# io-board-a-8.net
KiCad netlist of a schematic drawn in EAGLE
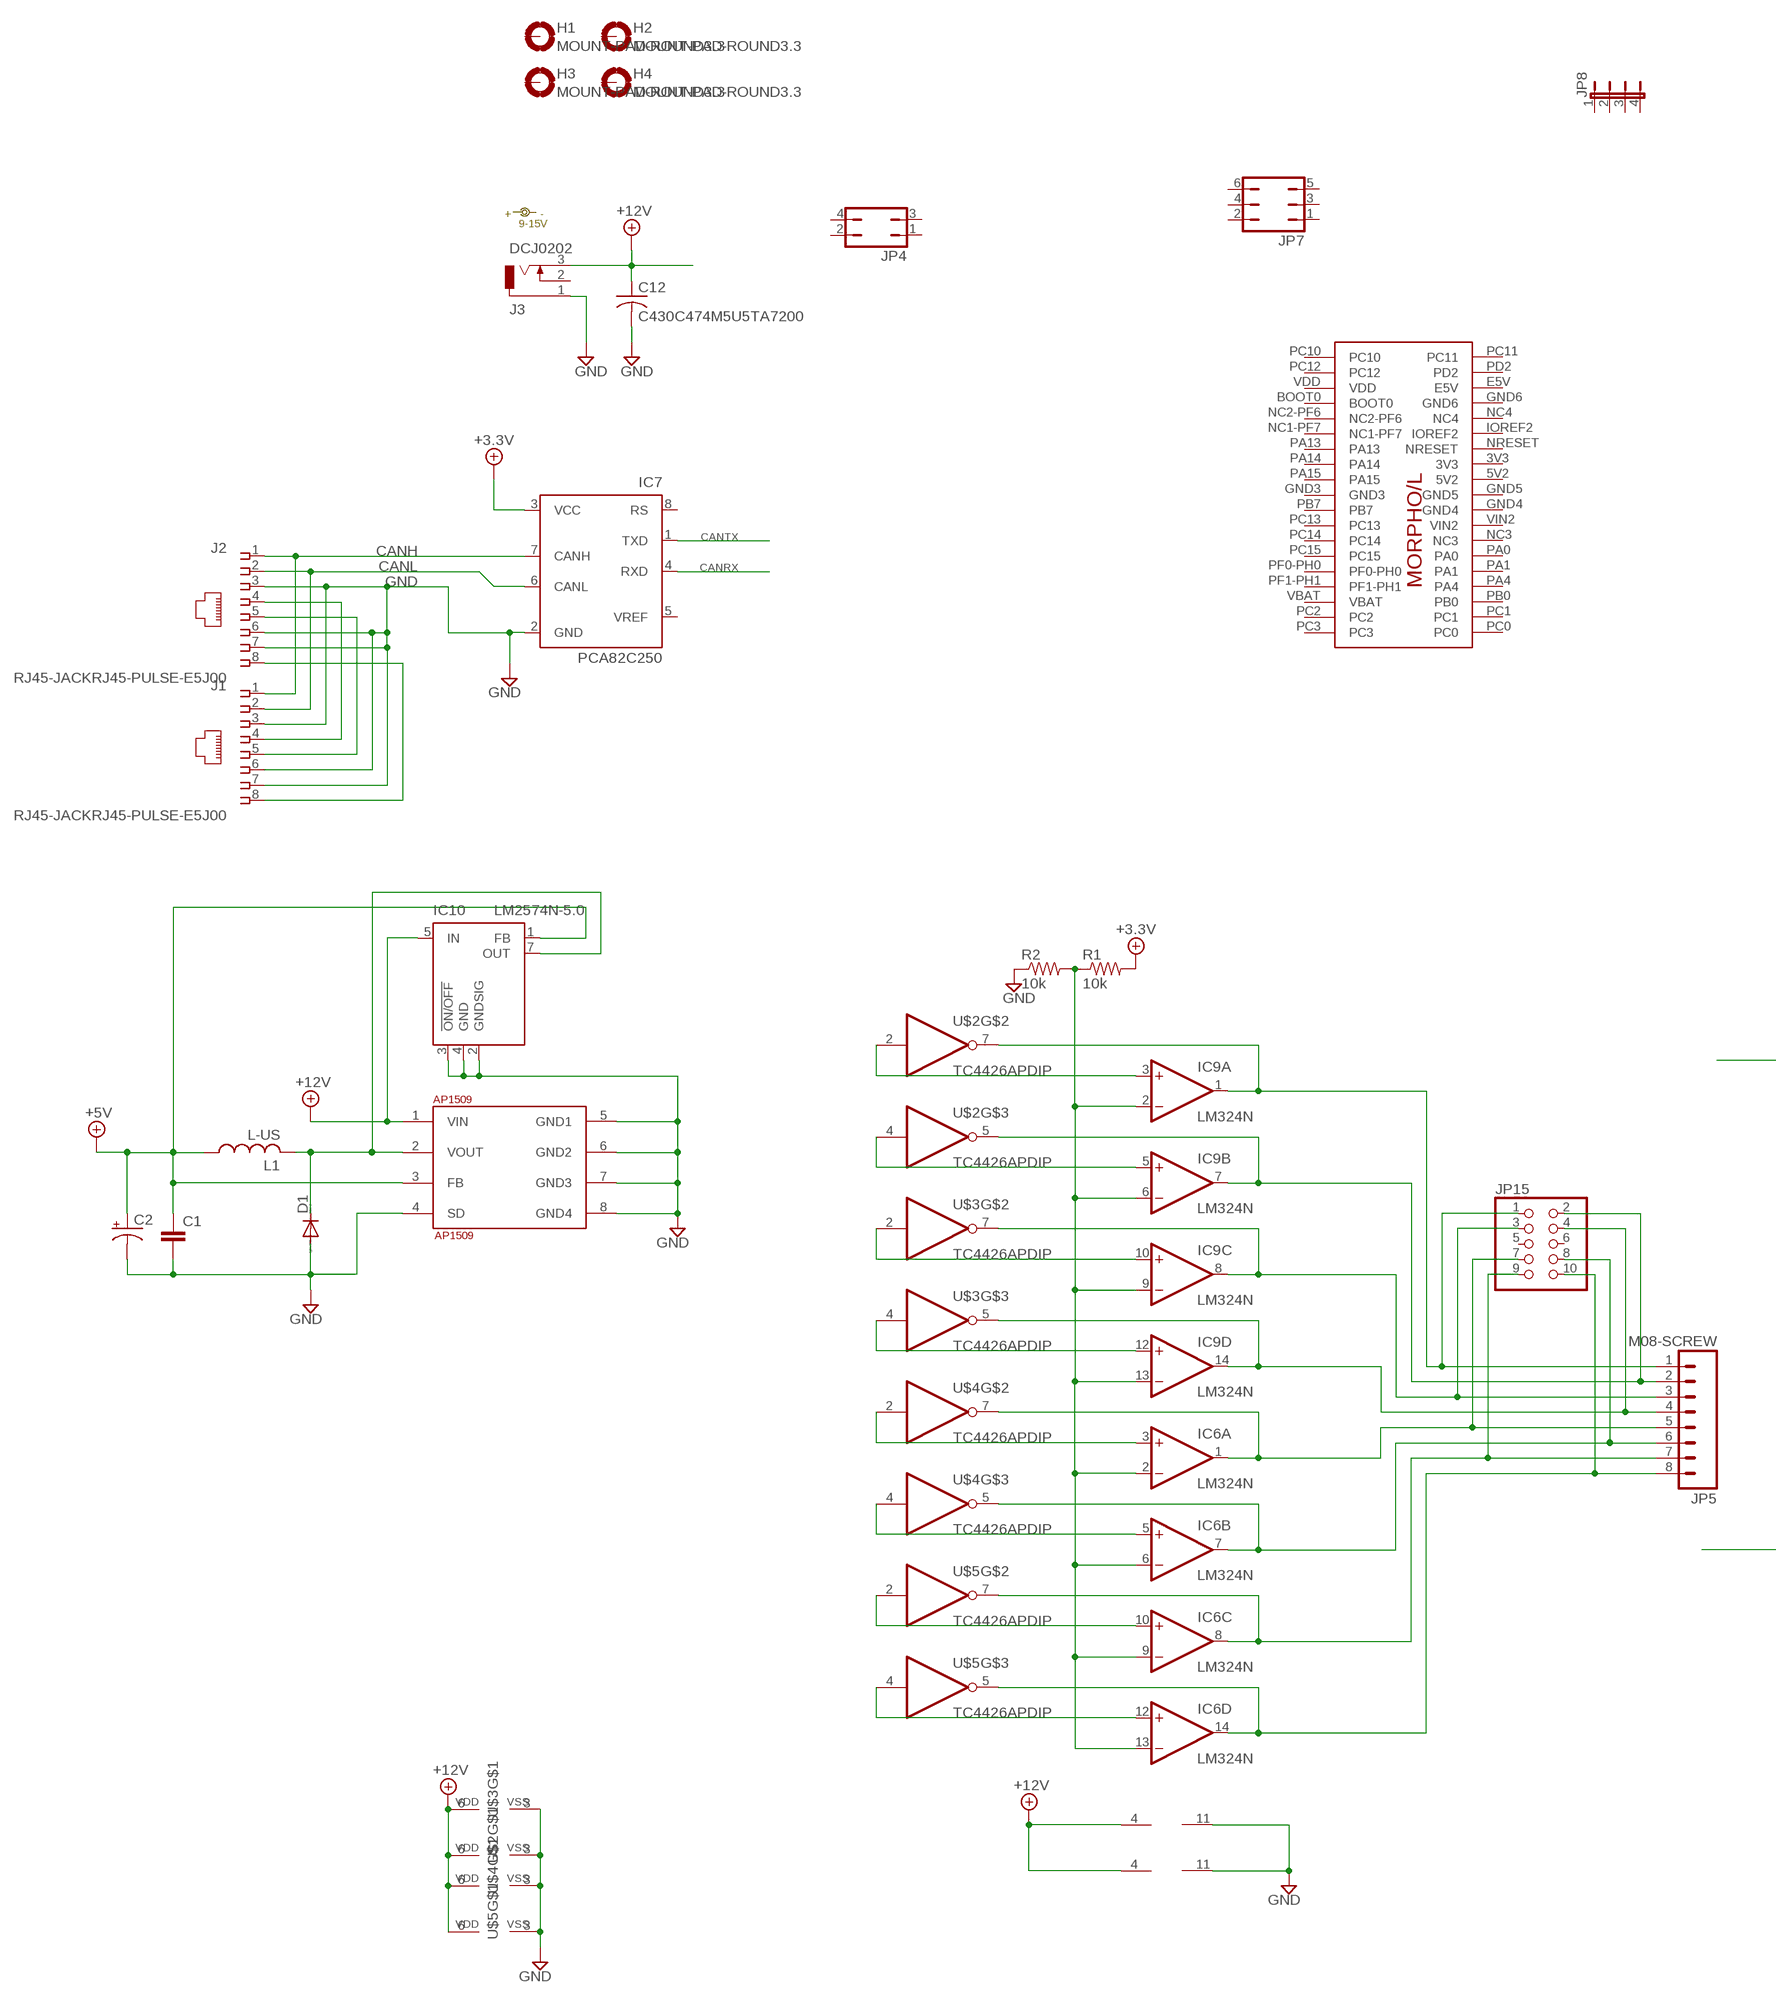
[diagram p0: schematic, sheet 1, part 1 of 2]
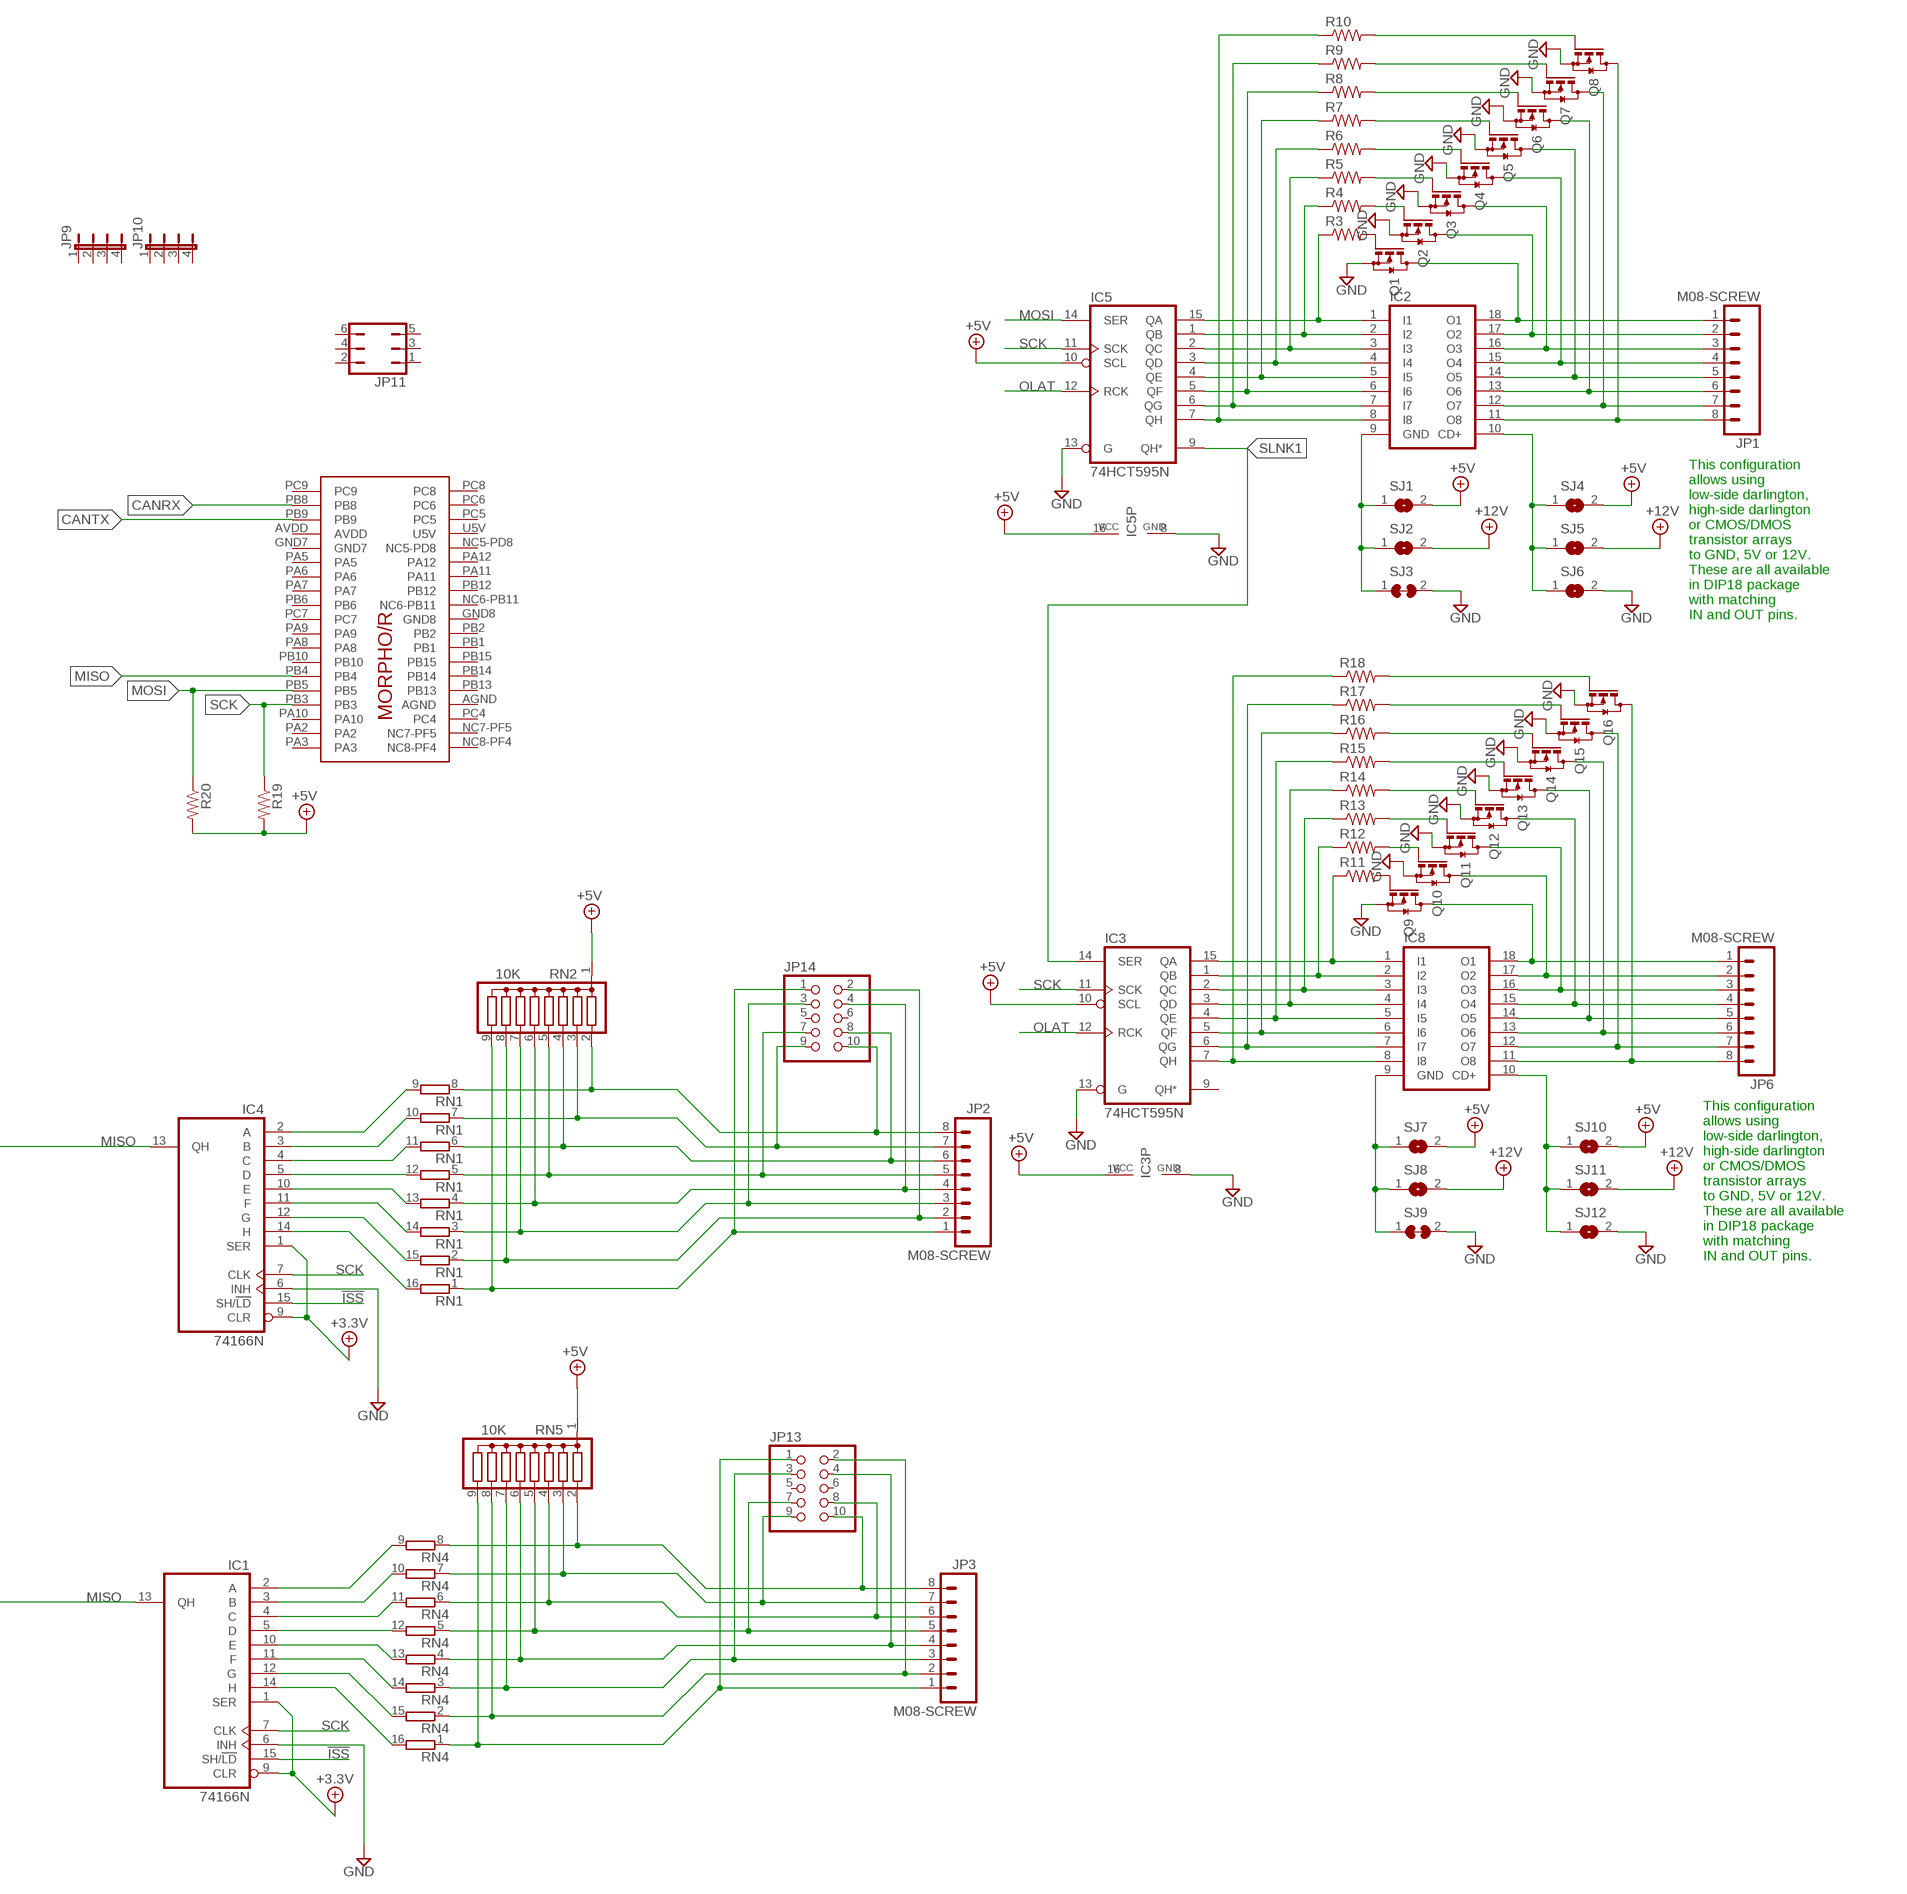
[diagram p1: schematic, sheet 1, part 2 of 2]

(export (version "E")
  (design (tool "Eeschema 10.0.6"))
  (components
    (comp (ref "+12V")
      (value "9-15V")
      (footprint "eagle-import:POWER_USAGE")
      (libsource (lib "eagle-import") (part "DOC-POWER_LABEL"))
    )
    (comp (ref "AP1509")
      (value "AP1509")
      (footprint "eagle-import:SO-08")
      (libsource (lib "eagle-import") (part "AP1509"))
    )
    (comp (ref "C1")
      (value "C-EUC1206")
      (footprint "eagle-import:C1206")
      (libsource (lib "eagle-import") (part "C-EUC1206"))
    )
    (comp (ref "C2")
      (value "CPOL-USE2.5-5")
      (footprint "eagle-import:E2,5-5")
      (libsource (lib "eagle-import") (part "CPOL-USE2.5-5"))
    )
    (comp (ref "C12")
      (value "C430C474M5U5TA7200")
      (footprint "eagle-import:C075-032X103")
      (libsource (lib "eagle-import") (part "C-US075-032X103"))
    )
    (comp (ref "D1")
      (value "DIODE-DO41-7.6")
      (footprint "eagle-import:DO41-7.6")
      (libsource (lib "eagle-import") (part "DIODE-DO41-7.6"))
    )
    (comp (ref "H1")
      (value "MOUNT-PAD-ROUND3.3")
      (footprint "eagle-import:3,3-PAD")
      (libsource (lib "eagle-import") (part "MOUNT-PAD-ROUND3.3"))
    )
    (comp (ref "H2")
      (value "MOUNT-PAD-ROUND3.3")
      (footprint "eagle-import:3,3-PAD")
      (libsource (lib "eagle-import") (part "MOUNT-PAD-ROUND3.3"))
    )
    (comp (ref "H3")
      (value "MOUNT-PAD-ROUND3.3")
      (footprint "eagle-import:3,3-PAD")
      (libsource (lib "eagle-import") (part "MOUNT-PAD-ROUND3.3"))
    )
    (comp (ref "H4")
      (value "MOUNT-PAD-ROUND3.3")
      (footprint "eagle-import:3,3-PAD")
      (libsource (lib "eagle-import") (part "MOUNT-PAD-ROUND3.3"))
    )
    (comp (ref "IC1")
      (value "74166N")
      (footprint "eagle-import:DIL16")
      (libsource (lib "eagle-import") (part "74166N"))
    )
    (comp (ref "IC2")
      (value "ULN2803A")
      (footprint "eagle-import:DIL18-THIN")
      (libsource (lib "eagle-import") (part "ULN2803A"))
    )
    (comp (ref "IC3")
      (value "74HCT595N")
      (footprint "eagle-import:DIL16")
      (libsource (lib "eagle-import") (part "74595NHCT"))
    )
    (comp (ref "IC4")
      (value "74166N")
      (footprint "eagle-import:DIL16")
      (libsource (lib "eagle-import") (part "74166N"))
    )
    (comp (ref "IC5")
      (value "74HCT595N")
      (footprint "eagle-import:DIL16")
      (libsource (lib "eagle-import") (part "74595NHCT"))
    )
    (comp (ref "IC6")
      (value "LM324N")
      (footprint "eagle-import:DIL14")
      (libsource (lib "eagle-import") (part "LM324N"))
    )
    (comp (ref "IC7")
      (value "PCA82C250")
      (footprint "eagle-import:DIL08")
      (libsource (lib "eagle-import") (part "PCA82C250"))
    )
    (comp (ref "IC8")
      (value "ULN2803A")
      (footprint "eagle-import:DIL18-THIN")
      (libsource (lib "eagle-import") (part "ULN2803A"))
    )
    (comp (ref "IC9")
      (value "LM324N")
      (footprint "eagle-import:DIL14")
      (libsource (lib "eagle-import") (part "LM324N"))
    )
    (comp (ref "IC10")
      (value "LM2574N-5.0")
      (footprint "eagle-import:DIL08")
      (libsource (lib "eagle-import") (part "LM2574?-N5.0"))
    )
    (comp (ref "J1")
      (value "RJ45-JACKRJ45-PULSE-E5J00")
      (footprint "eagle-import:RJ45-PULSE-E5J88")
      (libsource (lib "eagle-import") (part "RJ45-JACKRJ45-PULSE-E5J00"))
    )
    (comp (ref "J2")
      (value "RJ45-JACKRJ45-PULSE-E5J00")
      (footprint "eagle-import:RJ45-PULSE-E5J88")
      (libsource (lib "eagle-import") (part "RJ45-JACKRJ45-PULSE-E5J00"))
    )
    (comp (ref "J3")
      (value "DCJ0202")
      (footprint "eagle-import:DCJ0202")
      (libsource (lib "eagle-import") (part "DCJ0202"))
    )
    (comp (ref "JP1")
      (value "M08-SCREW")
      (footprint "eagle-import:1X08_TERMINAL")
      (libsource (lib "eagle-import") (part "M08-SCREW"))
    )
    (comp (ref "JP2")
      (value "M08-SCREW")
      (footprint "eagle-import:1X08_TERMINAL")
      (libsource (lib "eagle-import") (part "M08-SCREW"))
    )
    (comp (ref "JP3")
      (value "M08-SCREW")
      (footprint "eagle-import:1X08_TERMINAL")
      (libsource (lib "eagle-import") (part "M08-SCREW"))
    )
    (comp (ref "JP4")
      (value "JP2Q")
      (footprint "eagle-import:JP2Q")
      (libsource (lib "eagle-import") (part "JP2Q"))
    )
    (comp (ref "JP5")
      (value "M08-SCREW")
      (footprint "eagle-import:1X08_TERMINAL")
      (libsource (lib "eagle-import") (part "M08-SCREW"))
    )
    (comp (ref "JP6")
      (value "M08-SCREW")
      (footprint "eagle-import:1X08_TERMINAL")
      (libsource (lib "eagle-import") (part "M08-SCREW"))
    )
    (comp (ref "JP7")
      (value "JP3Q")
      (footprint "eagle-import:JP3Q")
      (libsource (lib "eagle-import") (part "JP3Q"))
    )
    (comp (ref "JP8")
      (value "JP4-FLAT")
      (footprint "eagle-import:JP4F")
      (libsource (lib "eagle-import") (part "JP4-FLAT"))
    )
    (comp (ref "JP9")
      (value "JP4-FLAT")
      (footprint "eagle-import:JP4F")
      (libsource (lib "eagle-import") (part "JP4-FLAT"))
    )
    (comp (ref "JP10")
      (value "JP4-FLAT")
      (footprint "eagle-import:JP4F")
      (libsource (lib "eagle-import") (part "JP4-FLAT"))
    )
    (comp (ref "JP11")
      (value "JP3Q")
      (footprint "eagle-import:JP3Q")
      (libsource (lib "eagle-import") (part "JP3Q"))
    )
    (comp (ref "JP13")
      (value "PINHD-2X5CN")
      (footprint "eagle-import:CON10M")
      (libsource (lib "eagle-import") (part "PINHD-2X5CN"))
    )
    (comp (ref "JP14")
      (value "PINHD-2X5CN")
      (footprint "eagle-import:CON10M")
      (libsource (lib "eagle-import") (part "PINHD-2X5CN"))
    )
    (comp (ref "JP15")
      (value "PINHD-2X5CN")
      (footprint "eagle-import:CON10M")
      (libsource (lib "eagle-import") (part "PINHD-2X5CN"))
    )
    (comp (ref "L1")
      (value "L-US")
      (footprint "eagle-import:L5-8,5")
      (libsource (lib "eagle-import") (part "L-US"))
    )
    (comp (ref "Q1")
      (value "BSS123")
      (footprint "eagle-import:SOT23")
      (libsource (lib "eagle-import") (part "BSS123"))
    )
    (comp (ref "Q2")
      (value "BSS123")
      (footprint "eagle-import:SOT23")
      (libsource (lib "eagle-import") (part "BSS123"))
    )
    (comp (ref "Q3")
      (value "BSS123")
      (footprint "eagle-import:SOT23")
      (libsource (lib "eagle-import") (part "BSS123"))
    )
    (comp (ref "Q4")
      (value "BSS123")
      (footprint "eagle-import:SOT23")
      (libsource (lib "eagle-import") (part "BSS123"))
    )
    (comp (ref "Q5")
      (value "BSS123")
      (footprint "eagle-import:SOT23")
      (libsource (lib "eagle-import") (part "BSS123"))
    )
    (comp (ref "Q6")
      (value "BSS123")
      (footprint "eagle-import:SOT23")
      (libsource (lib "eagle-import") (part "BSS123"))
    )
    (comp (ref "Q7")
      (value "BSS123")
      (footprint "eagle-import:SOT23")
      (libsource (lib "eagle-import") (part "BSS123"))
    )
    (comp (ref "Q8")
      (value "BSS123")
      (footprint "eagle-import:SOT23")
      (libsource (lib "eagle-import") (part "BSS123"))
    )
    (comp (ref "Q9")
      (value "BSS123")
      (footprint "eagle-import:SOT23")
      (libsource (lib "eagle-import") (part "BSS123"))
    )
    (comp (ref "Q10")
      (value "BSS123")
      (footprint "eagle-import:SOT23")
      (libsource (lib "eagle-import") (part "BSS123"))
    )
    (comp (ref "Q11")
      (value "BSS123")
      (footprint "eagle-import:SOT23")
      (libsource (lib "eagle-import") (part "BSS123"))
    )
    (comp (ref "Q12")
      (value "BSS123")
      (footprint "eagle-import:SOT23")
      (libsource (lib "eagle-import") (part "BSS123"))
    )
    (comp (ref "Q13")
      (value "BSS123")
      (footprint "eagle-import:SOT23")
      (libsource (lib "eagle-import") (part "BSS123"))
    )
    (comp (ref "Q14")
      (value "BSS123")
      (footprint "eagle-import:SOT23")
      (libsource (lib "eagle-import") (part "BSS123"))
    )
    (comp (ref "Q15")
      (value "BSS123")
      (footprint "eagle-import:SOT23")
      (libsource (lib "eagle-import") (part "BSS123"))
    )
    (comp (ref "Q16")
      (value "BSS123")
      (footprint "eagle-import:SOT23")
      (libsource (lib "eagle-import") (part "BSS123"))
    )
    (comp (ref "R1")
      (value "10k")
      (footprint "eagle-import:R1206")
      (libsource (lib "eagle-import") (part "R-US_R1206"))
    )
    (comp (ref "R2")
      (value "10k")
      (footprint "eagle-import:R1206")
      (libsource (lib "eagle-import") (part "R-US_R1206"))
    )
    (comp (ref "R3")
      (value "R-US_R0603")
      (footprint "eagle-import:R0603")
      (libsource (lib "eagle-import") (part "R-US_R0603"))
    )
    (comp (ref "R4")
      (value "R-US_R0603")
      (footprint "eagle-import:R0603")
      (libsource (lib "eagle-import") (part "R-US_R0603"))
    )
    (comp (ref "R5")
      (value "R-US_R0603")
      (footprint "eagle-import:R0603")
      (libsource (lib "eagle-import") (part "R-US_R0603"))
    )
    (comp (ref "R6")
      (value "R-US_R0603")
      (footprint "eagle-import:R0603")
      (libsource (lib "eagle-import") (part "R-US_R0603"))
    )
    (comp (ref "R7")
      (value "R-US_R0603")
      (footprint "eagle-import:R0603")
      (libsource (lib "eagle-import") (part "R-US_R0603"))
    )
    (comp (ref "R8")
      (value "R-US_R0603")
      (footprint "eagle-import:R0603")
      (libsource (lib "eagle-import") (part "R-US_R0603"))
    )
    (comp (ref "R9")
      (value "R-US_R0603")
      (footprint "eagle-import:R0603")
      (libsource (lib "eagle-import") (part "R-US_R0603"))
    )
    (comp (ref "R10")
      (value "R-US_R0603")
      (footprint "eagle-import:R0603")
      (libsource (lib "eagle-import") (part "R-US_R0603"))
    )
    (comp (ref "R11")
      (value "R-US_R0603")
      (footprint "eagle-import:R0603")
      (libsource (lib "eagle-import") (part "R-US_R0603"))
    )
    (comp (ref "R12")
      (value "R-US_R0603")
      (footprint "eagle-import:R0603")
      (libsource (lib "eagle-import") (part "R-US_R0603"))
    )
    (comp (ref "R13")
      (value "R-US_R0603")
      (footprint "eagle-import:R0603")
      (libsource (lib "eagle-import") (part "R-US_R0603"))
    )
    (comp (ref "R14")
      (value "R-US_R0603")
      (footprint "eagle-import:R0603")
      (libsource (lib "eagle-import") (part "R-US_R0603"))
    )
    (comp (ref "R15")
      (value "R-US_R0603")
      (footprint "eagle-import:R0603")
      (libsource (lib "eagle-import") (part "R-US_R0603"))
    )
    (comp (ref "R16")
      (value "R-US_R0603")
      (footprint "eagle-import:R0603")
      (libsource (lib "eagle-import") (part "R-US_R0603"))
    )
    (comp (ref "R17")
      (value "R-US_R0603")
      (footprint "eagle-import:R0603")
      (libsource (lib "eagle-import") (part "R-US_R0603"))
    )
    (comp (ref "R18")
      (value "R-US_R0603")
      (footprint "eagle-import:R0603")
      (libsource (lib "eagle-import") (part "R-US_R0603"))
    )
    (comp (ref "R19")
      (value "R-US_R0805")
      (footprint "eagle-import:R0805")
      (libsource (lib "eagle-import") (part "rcl_334_R-US_R0805"))
    )
    (comp (ref "R20")
      (value "R-US_R0805")
      (footprint "eagle-import:R0805")
      (libsource (lib "eagle-import") (part "rcl_334_R-US_R0805"))
    )
    (comp (ref "RN1")
      (value "8R-P")
      (footprint "eagle-import:DIL16")
      (libsource (lib "eagle-import") (part "8R-P"))
    )
    (comp (ref "RN2")
      (value "10K")
      (footprint "eagle-import:SIL9")
      (libsource (lib "eagle-import") (part "G08R"))
    )
    (comp (ref "RN4")
      (value "8R-P")
      (footprint "eagle-import:DIL16")
      (libsource (lib "eagle-import") (part "8R-P"))
    )
    (comp (ref "RN5")
      (value "10K")
      (footprint "eagle-import:SIL9")
      (libsource (lib "eagle-import") (part "G08R"))
    )
    (comp (ref "SJ1")
      (value "SJ")
      (footprint "eagle-import:SJ-RND")
      (libsource (lib "eagle-import") (part "SJ"))
    )
    (comp (ref "SJ2")
      (value "SJ")
      (footprint "eagle-import:SJ-RND")
      (libsource (lib "eagle-import") (part "SJ"))
    )
    (comp (ref "SJ3")
      (value "SJ-C")
      (footprint "eagle-import:SJW-C")
      (libsource (lib "eagle-import") (part "SJ-C"))
    )
    (comp (ref "SJ4")
      (value "SJ")
      (footprint "eagle-import:SJ-RND")
      (libsource (lib "eagle-import") (part "SJ"))
    )
    (comp (ref "SJ5")
      (value "SJ")
      (footprint "eagle-import:SJ-RND")
      (libsource (lib "eagle-import") (part "SJ"))
    )
    (comp (ref "SJ6")
      (value "SJ")
      (footprint "eagle-import:SJ-RND")
      (libsource (lib "eagle-import") (part "SJ"))
    )
    (comp (ref "SJ7")
      (value "SJ")
      (footprint "eagle-import:SJ-RND")
      (libsource (lib "eagle-import") (part "SJ"))
    )
    (comp (ref "SJ8")
      (value "SJ")
      (footprint "eagle-import:SJ-RND")
      (libsource (lib "eagle-import") (part "SJ"))
    )
    (comp (ref "SJ9")
      (value "SJ-C")
      (footprint "eagle-import:SJW-C")
      (libsource (lib "eagle-import") (part "SJ-C"))
    )
    (comp (ref "SJ10")
      (value "SJ")
      (footprint "eagle-import:SJ-RND")
      (libsource (lib "eagle-import") (part "SJ"))
    )
    (comp (ref "SJ11")
      (value "SJ")
      (footprint "eagle-import:SJ-RND")
      (libsource (lib "eagle-import") (part "SJ"))
    )
    (comp (ref "SJ12")
      (value "SJ")
      (footprint "eagle-import:SJ-RND")
      (libsource (lib "eagle-import") (part "SJ"))
    )
    (comp (ref "U$1")
      (value "NUCLEO_64_GENERIC")
      (footprint "eagle-import:NUCLEO_BRD_BASE64")
      (libsource (lib "eagle-import") (part "NUCLEO_64_GENERIC"))
    )
    (comp (ref "U$2")
      (value "TC4426APDIP")
      (footprint "eagle-import:DIL08-LONG")
      (libsource (lib "eagle-import") (part "TC4426APDIP"))
    )
    (comp (ref "U$3")
      (value "TC4426APDIP")
      (footprint "eagle-import:DIL08-LONG")
      (libsource (lib "eagle-import") (part "TC4426APDIP"))
    )
    (comp (ref "U$4")
      (value "TC4426APDIP")
      (footprint "eagle-import:DIL08-LONG")
      (libsource (lib "eagle-import") (part "TC4426APDIP"))
    )
    (comp (ref "U$5")
      (value "TC4426APDIP")
      (footprint "eagle-import:DIL08-LONG")
      (libsource (lib "eagle-import") (part "TC4426APDIP"))
    )
  )
  (nets
    (net (code "1") (name "+3.3V") (class "Default")
      (node (ref "IC1") (pin "1") (pinfunction "SER_1") (pintype "input"))
      (node (ref "IC1") (pin "9") (pinfunction "CLR_9") (pintype "input"))
      (node (ref "IC4") (pin "1") (pinfunction "SER_1") (pintype "input"))
      (node (ref "IC4") (pin "9") (pinfunction "CLR_9") (pintype "input"))
      (node (ref "IC7") (pin "3") (pinfunction "VCC_3") (pintype "power_in"))
      (node (ref "R1") (pin "2") (pinfunction "2_2") (pintype "passive"))
    )
    (net (code "2") (name "+5V") (class "Default")
      (node (ref "AP1509") (pin "3") (pinfunction "FB_3") (pintype "bidirectional"))
      (node (ref "C1") (pin "1") (pinfunction "1_1") (pintype "passive"))
      (node (ref "C2") (pin "+") (pinfunction "+_+") (pintype "passive"))
      (node (ref "IC10") (pin "1") (pinfunction "FB_1") (pintype "input"))
      (node (ref "IC3") (pin "10") (pinfunction "SCL_10") (pintype "input"))
      (node (ref "IC3") (pin "16") (pinfunction "VCC_16") (pintype "power_in"))
      (node (ref "IC5") (pin "10") (pinfunction "SCL_10") (pintype "input"))
      (node (ref "IC5") (pin "16") (pinfunction "VCC_16") (pintype "power_in"))
      (node (ref "L1") (pin "1") (pinfunction "1_1") (pintype "passive"))
      (node (ref "R19") (pin "2") (pinfunction "2_2") (pintype "passive"))
      (node (ref "R20") (pin "2") (pinfunction "2_2") (pintype "passive"))
      (node (ref "RN2") (pin "1") (pinfunction "1_1") (pintype "passive"))
      (node (ref "RN5") (pin "1") (pinfunction "1_1") (pintype "passive"))
      (node (ref "SJ1") (pin "2") (pinfunction "2_2") (pintype "passive"))
      (node (ref "SJ10") (pin "2") (pinfunction "2_2") (pintype "passive"))
      (node (ref "SJ4") (pin "2") (pinfunction "2_2") (pintype "passive"))
      (node (ref "SJ7") (pin "2") (pinfunction "2_2") (pintype "passive"))
    )
    (net (code "3") (name "+12V") (class "Default")
      (node (ref "AP1509") (pin "1") (pinfunction "VIN_1") (pintype "bidirectional"))
      (node (ref "C12") (pin "1") (pinfunction "1_1") (pintype "passive"))
      (node (ref "IC10") (pin "5") (pinfunction "IN_5") (pintype "input"))
      (node (ref "IC6") (pin "4") (pinfunction "V+_4") (pintype "power_in"))
      (node (ref "IC9") (pin "4") (pinfunction "V+_4") (pintype "power_in"))
      (node (ref "J3") (pin "3") (pinfunction "3_3") (pintype "passive"))
      (node (ref "SJ11") (pin "2") (pinfunction "2_2") (pintype "passive"))
      (node (ref "SJ2") (pin "2") (pinfunction "2_2") (pintype "passive"))
      (node (ref "SJ5") (pin "2") (pinfunction "2_2") (pintype "passive"))
      (node (ref "SJ8") (pin "2") (pinfunction "2_2") (pintype "passive"))
      (node (ref "U$2") (pin "6") (pinfunction "VDD_6") (pintype "power_in"))
      (node (ref "U$3") (pin "6") (pinfunction "VDD_6") (pintype "power_in"))
      (node (ref "U$4") (pin "6") (pinfunction "VDD_6") (pintype "power_in"))
      (node (ref "U$5") (pin "6") (pinfunction "VDD_6") (pintype "power_in"))
    )
    (net (code "4") (name "/3V3") (class "Default")
      (node (ref "U$1") (pin "3V3") (pinfunction "3V3_3V3") (pintype "power_in"))
    )
    (net (code "5") (name "/5V2") (class "Default")
      (node (ref "U$1") (pin "5V2") (pinfunction "5V2_5V2") (pintype "power_in"))
    )
    (net (code "6") (name "/AGND") (class "Default")
      (node (ref "U$1") (pin "AGND") (pinfunction "AGND_AGND") (pintype "power_in"))
    )
    (net (code "7") (name "/AVDD") (class "Default")
      (node (ref "U$1") (pin "AVDD") (pinfunction "AVDD_AVDD") (pintype "power_in"))
    )
    (net (code "8") (name "/CANH") (class "Default")
      (node (ref "IC7") (pin "7") (pinfunction "CANH_7") (pintype "bidirectional"))
      (node (ref "J1") (pin "1") (pinfunction "1_1") (pintype "passive"))
      (node (ref "J2") (pin "1") (pinfunction "1_1") (pintype "passive"))
    )
    (net (code "9") (name "/CANL") (class "Default")
      (node (ref "IC7") (pin "6") (pinfunction "CANL_6") (pintype "bidirectional"))
      (node (ref "J1") (pin "2") (pinfunction "2_2") (pintype "passive"))
      (node (ref "J2") (pin "2") (pinfunction "2_2") (pintype "passive"))
    )
    (net (code "10") (name "/E5V") (class "Default")
      (node (ref "U$1") (pin "E5V") (pinfunction "E5V_E5V") (pintype "power_in"))
    )
    (net (code "11") (name "/GND3") (class "Default")
      (node (ref "U$1") (pin "GND3") (pinfunction "GND3_GND3") (pintype "power_in"))
    )
    (net (code "12") (name "/GND4") (class "Default")
      (node (ref "U$1") (pin "GND4") (pinfunction "GND4_GND4") (pintype "power_in"))
    )
    (net (code "13") (name "/GND5") (class "Default")
      (node (ref "U$1") (pin "GND5") (pinfunction "GND5_GND5") (pintype "power_in"))
    )
    (net (code "14") (name "/GND6") (class "Default")
      (node (ref "U$1") (pin "GND6") (pinfunction "GND6_GND6") (pintype "power_in"))
    )
    (net (code "15") (name "/GND7") (class "Default")
      (node (ref "U$1") (pin "GND7") (pinfunction "GND7_GND7") (pintype "power_in"))
    )
    (net (code "16") (name "/GND8") (class "Default")
      (node (ref "U$1") (pin "GND8") (pinfunction "GND8_GND8") (pintype "power_in"))
    )
    (net (code "17") (name "/OLAT") (class "Default")
      (node (ref "IC3") (pin "12") (pinfunction "RCK_12") (pintype "input"))
      (node (ref "IC5") (pin "12") (pinfunction "RCK_12") (pintype "input"))
    )
    (net (code "18") (name "/U5V") (class "Default")
      (node (ref "U$1") (pin "U5V") (pinfunction "U5V_U5V") (pintype "power_in"))
    )
    (net (code "19") (name "/VBAT") (class "Default")
      (node (ref "U$1") (pin "VBAT") (pinfunction "VBAT_VBAT") (pintype "power_in"))
    )
    (net (code "20") (name "/VDD") (class "Default")
      (node (ref "U$1") (pin "VDD") (pinfunction "VDD_VDD") (pintype "power_in"))
    )
    (net (code "21") (name "/VIN2") (class "Default")
      (node (ref "U$1") (pin "VIN2") (pinfunction "VIN2_VIN2") (pintype "power_in"))
    )
    (net (code "22") (name "/~{ISS}") (class "Default")
      (node (ref "IC1") (pin "15") (pinfunction "SH/~{LD}_15") (pintype "input"))
      (node (ref "IC4") (pin "15") (pinfunction "SH/~{LD}_15") (pintype "input"))
    )
    (net (code "23") (name "CANRX") (class "Default")
      (node (ref "IC7") (pin "4") (pinfunction "RXD_4") (pintype "output"))
      (node (ref "U$1") (pin "PB8") (pinfunction "PB8_PB8") (pintype "bidirectional"))
    )
    (net (code "24") (name "CANTX") (class "Default")
      (node (ref "IC7") (pin "1") (pinfunction "TXD_1") (pintype "input"))
      (node (ref "U$1") (pin "PB9") (pinfunction "PB9_PB9") (pintype "bidirectional"))
    )
    (net (code "25") (name "GND") (class "Default")
      (node (ref "AP1509") (pin "4") (pinfunction "SD_4") (pintype "bidirectional"))
      (node (ref "AP1509") (pin "5") (pinfunction "GND1_5") (pintype "power_in"))
      (node (ref "AP1509") (pin "6") (pinfunction "GND2_6") (pintype "power_in"))
      (node (ref "AP1509") (pin "7") (pinfunction "GND3_7") (pintype "power_in"))
      (node (ref "AP1509") (pin "8") (pinfunction "GND4_8") (pintype "power_in"))
      (node (ref "C1") (pin "2") (pinfunction "2_2") (pintype "passive"))
      (node (ref "C12") (pin "2") (pinfunction "2_2") (pintype "passive"))
      (node (ref "C2") (pin "-") (pinfunction "-_-") (pintype "passive"))
      (node (ref "D1") (pin "A") (pinfunction "A_A") (pintype "passive"))
      (node (ref "IC1") (pin "6") (pinfunction "INH_6") (pintype "input"))
      (node (ref "IC10") (pin "2") (pinfunction "GNDSIG_2") (pintype "input"))
      (node (ref "IC10") (pin "3") (pinfunction "~{ON/OFF}_3") (pintype "input"))
      (node (ref "IC10") (pin "4") (pinfunction "GND_4") (pintype "power_in"))
      (node (ref "IC3") (pin "13") (pinfunction "G_13") (pintype "input"))
      (node (ref "IC3") (pin "8") (pinfunction "GND_8") (pintype "power_in"))
      (node (ref "IC4") (pin "6") (pinfunction "INH_6") (pintype "input"))
      (node (ref "IC5") (pin "13") (pinfunction "G_13") (pintype "input"))
      (node (ref "IC5") (pin "8") (pinfunction "GND_8") (pintype "power_in"))
      (node (ref "IC6") (pin "11") (pinfunction "V-_11") (pintype "power_in"))
      (node (ref "IC7") (pin "2") (pinfunction "GND_2") (pintype "power_in"))
      (node (ref "IC9") (pin "11") (pinfunction "V-_11") (pintype "power_in"))
      (node (ref "J1") (pin "3") (pinfunction "3_3") (pintype "passive"))
      (node (ref "J1") (pin "6") (pinfunction "6_6") (pintype "passive"))
      (node (ref "J1") (pin "7") (pinfunction "7_7") (pintype "passive"))
      (node (ref "J2") (pin "3") (pinfunction "3_3") (pintype "passive"))
      (node (ref "J2") (pin "6") (pinfunction "6_6") (pintype "passive"))
      (node (ref "J2") (pin "7") (pinfunction "7_7") (pintype "passive"))
      (node (ref "J3") (pin "1") (pinfunction "1_1") (pintype "passive"))
      (node (ref "Q1") (pin "2") (pinfunction "S_2") (pintype "passive"))
      (node (ref "Q10") (pin "2") (pinfunction "S_2") (pintype "passive"))
      (node (ref "Q11") (pin "2") (pinfunction "S_2") (pintype "passive"))
      (node (ref "Q12") (pin "2") (pinfunction "S_2") (pintype "passive"))
      (node (ref "Q13") (pin "2") (pinfunction "S_2") (pintype "passive"))
      (node (ref "Q14") (pin "2") (pinfunction "S_2") (pintype "passive"))
      (node (ref "Q15") (pin "2") (pinfunction "S_2") (pintype "passive"))
      (node (ref "Q16") (pin "2") (pinfunction "S_2") (pintype "passive"))
      (node (ref "Q2") (pin "2") (pinfunction "S_2") (pintype "passive"))
      (node (ref "Q3") (pin "2") (pinfunction "S_2") (pintype "passive"))
      (node (ref "Q4") (pin "2") (pinfunction "S_2") (pintype "passive"))
      (node (ref "Q5") (pin "2") (pinfunction "S_2") (pintype "passive"))
      (node (ref "Q6") (pin "2") (pinfunction "S_2") (pintype "passive"))
      (node (ref "Q7") (pin "2") (pinfunction "S_2") (pintype "passive"))
      (node (ref "Q8") (pin "2") (pinfunction "S_2") (pintype "passive"))
      (node (ref "Q9") (pin "2") (pinfunction "S_2") (pintype "passive"))
      (node (ref "R2") (pin "1") (pinfunction "1_1") (pintype "passive"))
      (node (ref "SJ12") (pin "2") (pinfunction "2_2") (pintype "passive"))
      (node (ref "SJ3") (pin "2") (pinfunction "2_2") (pintype "passive"))
      (node (ref "SJ6") (pin "2") (pinfunction "2_2") (pintype "passive"))
      (node (ref "SJ9") (pin "2") (pinfunction "2_2") (pintype "passive"))
      (node (ref "U$2") (pin "3") (pinfunction "VSS_3") (pintype "power_in"))
      (node (ref "U$3") (pin "3") (pinfunction "VSS_3") (pintype "power_in"))
      (node (ref "U$4") (pin "3") (pinfunction "VSS_3") (pintype "power_in"))
      (node (ref "U$5") (pin "3") (pinfunction "VSS_3") (pintype "power_in"))
    )
    (net (code "26") (name "MISO") (class "Default")
      (node (ref "IC1") (pin "13") (pinfunction "QH_13") (pintype "output"))
      (node (ref "IC4") (pin "13") (pinfunction "QH_13") (pintype "output"))
      (node (ref "U$1") (pin "PB4") (pinfunction "PB4_PB4") (pintype "bidirectional"))
    )
    (net (code "27") (name "MOSI") (class "Default")
      (node (ref "IC5") (pin "14") (pinfunction "SER_14") (pintype "input"))
      (node (ref "R20") (pin "1") (pinfunction "1_1") (pintype "passive"))
      (node (ref "U$1") (pin "PB5") (pinfunction "PB5_PB5") (pintype "bidirectional"))
    )
    (net (code "28") (name "Net-(AP1509-VOUT)") (class "Default")
      (node (ref "AP1509") (pin "2") (pinfunction "VOUT_2") (pintype "bidirectional"))
      (node (ref "D1") (pin "C") (pinfunction "C_C") (pintype "passive"))
      (node (ref "IC10") (pin "7") (pinfunction "OUT_7") (pintype "passive"))
      (node (ref "L1") (pin "2") (pinfunction "2_2") (pintype "passive"))
    )
    (net (code "29") (name "Net-(IC1A-A)") (class "Default")
      (node (ref "IC1") (pin "2") (pinfunction "A_2") (pintype "input"))
      (node (ref "RN4") (pin "9") (pinfunction "2_9") (pintype "passive"))
    )
    (net (code "30") (name "Net-(IC1A-B)") (class "Default")
      (node (ref "IC1") (pin "3") (pinfunction "B_3") (pintype "input"))
      (node (ref "RN4") (pin "10") (pinfunction "2_10") (pintype "passive"))
    )
    (net (code "31") (name "Net-(IC1A-C)") (class "Default")
      (node (ref "IC1") (pin "4") (pinfunction "C_4") (pintype "input"))
      (node (ref "RN4") (pin "11") (pinfunction "2_11") (pintype "passive"))
    )
    (net (code "32") (name "Net-(IC1A-D)") (class "Default")
      (node (ref "IC1") (pin "5") (pinfunction "D_5") (pintype "input"))
      (node (ref "RN4") (pin "12") (pinfunction "2_12") (pintype "passive"))
    )
    (net (code "33") (name "Net-(IC1A-E)") (class "Default")
      (node (ref "IC1") (pin "10") (pinfunction "E_10") (pintype "input"))
      (node (ref "RN4") (pin "13") (pinfunction "2_13") (pintype "passive"))
    )
    (net (code "34") (name "Net-(IC1A-F)") (class "Default")
      (node (ref "IC1") (pin "11") (pinfunction "F_11") (pintype "input"))
      (node (ref "RN4") (pin "14") (pinfunction "2_14") (pintype "passive"))
    )
    (net (code "35") (name "Net-(IC1A-G)") (class "Default")
      (node (ref "IC1") (pin "12") (pinfunction "G_12") (pintype "input"))
      (node (ref "RN4") (pin "15") (pinfunction "2_15") (pintype "passive"))
    )
    (net (code "36") (name "Net-(IC1A-H)") (class "Default")
      (node (ref "IC1") (pin "14") (pinfunction "H_14") (pintype "input"))
      (node (ref "RN4") (pin "16") (pinfunction "2_16") (pintype "passive"))
    )
    (net (code "37") (name "Net-(IC2-CD+)") (class "Default")
      (node (ref "IC2") (pin "10") (pinfunction "CD+_10") (pintype "passive"))
      (node (ref "SJ4") (pin "1") (pinfunction "1_1") (pintype "passive"))
      (node (ref "SJ5") (pin "1") (pinfunction "1_1") (pintype "passive"))
      (node (ref "SJ6") (pin "1") (pinfunction "1_1") (pintype "passive"))
    )
    (net (code "38") (name "Net-(IC2-GND)") (class "Default")
      (node (ref "IC2") (pin "9") (pinfunction "GND_9") (pintype "power_in"))
      (node (ref "SJ1") (pin "1") (pinfunction "1_1") (pintype "passive"))
      (node (ref "SJ2") (pin "1") (pinfunction "1_1") (pintype "passive"))
      (node (ref "SJ3") (pin "1") (pinfunction "1_1") (pintype "passive"))
    )
    (net (code "39") (name "Net-(IC2-I1)") (class "Default")
      (node (ref "IC2") (pin "1") (pinfunction "I1_1") (pintype "input"))
      (node (ref "IC5") (pin "15") (pinfunction "QA_15") (pintype "tri_state"))
      (node (ref "R3") (pin "1") (pinfunction "1_1") (pintype "passive"))
    )
    (net (code "40") (name "Net-(IC2-I2)") (class "Default")
      (node (ref "IC2") (pin "2") (pinfunction "I2_2") (pintype "input"))
      (node (ref "IC5") (pin "1") (pinfunction "QB_1") (pintype "tri_state"))
      (node (ref "R4") (pin "1") (pinfunction "1_1") (pintype "passive"))
    )
    (net (code "41") (name "Net-(IC2-I3)") (class "Default")
      (node (ref "IC2") (pin "3") (pinfunction "I3_3") (pintype "input"))
      (node (ref "IC5") (pin "2") (pinfunction "QC_2") (pintype "tri_state"))
      (node (ref "R5") (pin "1") (pinfunction "1_1") (pintype "passive"))
    )
    (net (code "42") (name "Net-(IC2-I4)") (class "Default")
      (node (ref "IC2") (pin "4") (pinfunction "I4_4") (pintype "input"))
      (node (ref "IC5") (pin "3") (pinfunction "QD_3") (pintype "tri_state"))
      (node (ref "R6") (pin "1") (pinfunction "1_1") (pintype "passive"))
    )
    (net (code "43") (name "Net-(IC2-I5)") (class "Default")
      (node (ref "IC2") (pin "5") (pinfunction "I5_5") (pintype "input"))
      (node (ref "IC5") (pin "4") (pinfunction "QE_4") (pintype "tri_state"))
      (node (ref "R7") (pin "1") (pinfunction "1_1") (pintype "passive"))
    )
    (net (code "44") (name "Net-(IC2-I6)") (class "Default")
      (node (ref "IC2") (pin "6") (pinfunction "I6_6") (pintype "input"))
      (node (ref "IC5") (pin "5") (pinfunction "QF_5") (pintype "tri_state"))
      (node (ref "R8") (pin "1") (pinfunction "1_1") (pintype "passive"))
    )
    (net (code "45") (name "Net-(IC2-I7)") (class "Default")
      (node (ref "IC2") (pin "7") (pinfunction "I7_7") (pintype "input"))
      (node (ref "IC5") (pin "6") (pinfunction "QG_6") (pintype "tri_state"))
      (node (ref "R9") (pin "1") (pinfunction "1_1") (pintype "passive"))
    )
    (net (code "46") (name "Net-(IC2-I8)") (class "Default")
      (node (ref "IC2") (pin "8") (pinfunction "I8_8") (pintype "input"))
      (node (ref "IC5") (pin "7") (pinfunction "QH_7") (pintype "tri_state"))
      (node (ref "R10") (pin "1") (pinfunction "1_1") (pintype "passive"))
    )
    (net (code "47") (name "Net-(IC2-O1)") (class "Default")
      (node (ref "IC2") (pin "18") (pinfunction "O1_18") (pintype "open_collector"))
      (node (ref "JP1") (pin "1") (pinfunction "1_1") (pintype "passive"))
      (node (ref "Q1") (pin "3") (pinfunction "D_3") (pintype "passive"))
    )
    (net (code "48") (name "Net-(IC2-O2)") (class "Default")
      (node (ref "IC2") (pin "17") (pinfunction "O2_17") (pintype "open_collector"))
      (node (ref "JP1") (pin "2") (pinfunction "2_2") (pintype "passive"))
      (node (ref "Q2") (pin "3") (pinfunction "D_3") (pintype "passive"))
    )
    (net (code "49") (name "Net-(IC2-O3)") (class "Default")
      (node (ref "IC2") (pin "16") (pinfunction "O3_16") (pintype "open_collector"))
      (node (ref "JP1") (pin "3") (pinfunction "3_3") (pintype "passive"))
      (node (ref "Q3") (pin "3") (pinfunction "D_3") (pintype "passive"))
    )
    (net (code "50") (name "Net-(IC2-O4)") (class "Default")
      (node (ref "IC2") (pin "15") (pinfunction "O4_15") (pintype "open_collector"))
      (node (ref "JP1") (pin "4") (pinfunction "4_4") (pintype "passive"))
      (node (ref "Q4") (pin "3") (pinfunction "D_3") (pintype "passive"))
    )
    (net (code "51") (name "Net-(IC2-O5)") (class "Default")
      (node (ref "IC2") (pin "14") (pinfunction "O5_14") (pintype "open_collector"))
      (node (ref "JP1") (pin "5") (pinfunction "5_5") (pintype "passive"))
      (node (ref "Q5") (pin "3") (pinfunction "D_3") (pintype "passive"))
    )
    (net (code "52") (name "Net-(IC2-O6)") (class "Default")
      (node (ref "IC2") (pin "13") (pinfunction "O6_13") (pintype "open_collector"))
      (node (ref "JP1") (pin "6") (pinfunction "6_6") (pintype "passive"))
      (node (ref "Q6") (pin "3") (pinfunction "D_3") (pintype "passive"))
    )
    (net (code "53") (name "Net-(IC2-O7)") (class "Default")
      (node (ref "IC2") (pin "12") (pinfunction "O7_12") (pintype "open_collector"))
      (node (ref "JP1") (pin "7") (pinfunction "7_7") (pintype "passive"))
      (node (ref "Q7") (pin "3") (pinfunction "D_3") (pintype "passive"))
    )
    (net (code "54") (name "Net-(IC2-O8)") (class "Default")
      (node (ref "IC2") (pin "11") (pinfunction "O8_11") (pintype "open_collector"))
      (node (ref "JP1") (pin "8") (pinfunction "8_8") (pintype "passive"))
      (node (ref "Q8") (pin "3") (pinfunction "D_3") (pintype "passive"))
    )
    (net (code "55") (name "Net-(IC3A-QA)") (class "Default")
      (node (ref "IC3") (pin "15") (pinfunction "QA_15") (pintype "tri_state"))
      (node (ref "IC8") (pin "1") (pinfunction "I1_1") (pintype "input"))
      (node (ref "R11") (pin "1") (pinfunction "1_1") (pintype "passive"))
    )
    (net (code "56") (name "Net-(IC3A-QB)") (class "Default")
      (node (ref "IC3") (pin "1") (pinfunction "QB_1") (pintype "tri_state"))
      (node (ref "IC8") (pin "2") (pinfunction "I2_2") (pintype "input"))
      (node (ref "R12") (pin "1") (pinfunction "1_1") (pintype "passive"))
    )
    (net (code "57") (name "Net-(IC3A-QC)") (class "Default")
      (node (ref "IC3") (pin "2") (pinfunction "QC_2") (pintype "tri_state"))
      (node (ref "IC8") (pin "3") (pinfunction "I3_3") (pintype "input"))
      (node (ref "R13") (pin "1") (pinfunction "1_1") (pintype "passive"))
    )
    (net (code "58") (name "Net-(IC3A-QD)") (class "Default")
      (node (ref "IC3") (pin "3") (pinfunction "QD_3") (pintype "tri_state"))
      (node (ref "IC8") (pin "4") (pinfunction "I4_4") (pintype "input"))
      (node (ref "R14") (pin "1") (pinfunction "1_1") (pintype "passive"))
    )
    (net (code "59") (name "Net-(IC3A-QE)") (class "Default")
      (node (ref "IC3") (pin "4") (pinfunction "QE_4") (pintype "tri_state"))
      (node (ref "IC8") (pin "5") (pinfunction "I5_5") (pintype "input"))
      (node (ref "R15") (pin "1") (pinfunction "1_1") (pintype "passive"))
    )
    (net (code "60") (name "Net-(IC3A-QF)") (class "Default")
      (node (ref "IC3") (pin "5") (pinfunction "QF_5") (pintype "tri_state"))
      (node (ref "IC8") (pin "6") (pinfunction "I6_6") (pintype "input"))
      (node (ref "R16") (pin "1") (pinfunction "1_1") (pintype "passive"))
    )
    (net (code "61") (name "Net-(IC3A-QG)") (class "Default")
      (node (ref "IC3") (pin "6") (pinfunction "QG_6") (pintype "tri_state"))
      (node (ref "IC8") (pin "7") (pinfunction "I7_7") (pintype "input"))
      (node (ref "R17") (pin "1") (pinfunction "1_1") (pintype "passive"))
    )
    (net (code "62") (name "Net-(IC3A-QH)") (class "Default")
      (node (ref "IC3") (pin "7") (pinfunction "QH_7") (pintype "tri_state"))
      (node (ref "IC8") (pin "8") (pinfunction "I8_8") (pintype "input"))
      (node (ref "R18") (pin "1") (pinfunction "1_1") (pintype "passive"))
    )
    (net (code "63") (name "Net-(IC4A-A)") (class "Default")
      (node (ref "IC4") (pin "2") (pinfunction "A_2") (pintype "input"))
      (node (ref "RN1") (pin "9") (pinfunction "2_9") (pintype "passive"))
    )
    (net (code "64") (name "Net-(IC4A-B)") (class "Default")
      (node (ref "IC4") (pin "3") (pinfunction "B_3") (pintype "input"))
      (node (ref "RN1") (pin "10") (pinfunction "2_10") (pintype "passive"))
    )
    (net (code "65") (name "Net-(IC4A-C)") (class "Default")
      (node (ref "IC4") (pin "4") (pinfunction "C_4") (pintype "input"))
      (node (ref "RN1") (pin "11") (pinfunction "2_11") (pintype "passive"))
    )
    (net (code "66") (name "Net-(IC4A-D)") (class "Default")
      (node (ref "IC4") (pin "5") (pinfunction "D_5") (pintype "input"))
      (node (ref "RN1") (pin "12") (pinfunction "2_12") (pintype "passive"))
    )
    (net (code "67") (name "Net-(IC4A-E)") (class "Default")
      (node (ref "IC4") (pin "10") (pinfunction "E_10") (pintype "input"))
      (node (ref "RN1") (pin "13") (pinfunction "2_13") (pintype "passive"))
    )
    (net (code "68") (name "Net-(IC4A-F)") (class "Default")
      (node (ref "IC4") (pin "11") (pinfunction "F_11") (pintype "input"))
      (node (ref "RN1") (pin "14") (pinfunction "2_14") (pintype "passive"))
    )
    (net (code "69") (name "Net-(IC4A-G)") (class "Default")
      (node (ref "IC4") (pin "12") (pinfunction "G_12") (pintype "input"))
      (node (ref "RN1") (pin "15") (pinfunction "2_15") (pintype "passive"))
    )
    (net (code "70") (name "Net-(IC4A-H)") (class "Default")
      (node (ref "IC4") (pin "14") (pinfunction "H_14") (pintype "input"))
      (node (ref "RN1") (pin "16") (pinfunction "2_16") (pintype "passive"))
    )
    (net (code "71") (name "Net-(IC6A-+IN)") (class "Default")
      (node (ref "IC6") (pin "3") (pinfunction "+IN_3") (pintype "input"))
      (node (ref "U$4") (pin "2") (pinfunction "I_2") (pintype "input"))
    )
    (net (code "72") (name "Net-(IC6A--IN)") (class "Default")
      (node (ref "IC6") (pin "13") (pinfunction "-IN_13") (pintype "input"))
      (node (ref "IC6") (pin "2") (pinfunction "-IN_2") (pintype "input"))
      (node (ref "IC6") (pin "6") (pinfunction "-IN_6") (pintype "input"))
      (node (ref "IC6") (pin "9") (pinfunction "-IN_9") (pintype "input"))
      (node (ref "IC9") (pin "13") (pinfunction "-IN_13") (pintype "input"))
      (node (ref "IC9") (pin "2") (pinfunction "-IN_2") (pintype "input"))
      (node (ref "IC9") (pin "6") (pinfunction "-IN_6") (pintype "input"))
      (node (ref "IC9") (pin "9") (pinfunction "-IN_9") (pintype "input"))
      (node (ref "R1") (pin "1") (pinfunction "1_1") (pintype "passive"))
      (node (ref "R2") (pin "2") (pinfunction "2_2") (pintype "passive"))
    )
    (net (code "73") (name "Net-(IC6A-OUT)") (class "Default")
      (node (ref "IC6") (pin "1") (pinfunction "OUT_1") (pintype "output"))
      (node (ref "JP15") (pin "7") (pinfunction "7_7") (pintype "passive"))
      (node (ref "JP5") (pin "5") (pinfunction "5_5") (pintype "passive"))
      (node (ref "U$4") (pin "7") (pinfunction "O_7") (pintype "output"))
    )
    (net (code "74") (name "Net-(IC6B-+IN)") (class "Default")
      (node (ref "IC6") (pin "5") (pinfunction "+IN_5") (pintype "input"))
      (node (ref "U$4") (pin "4") (pinfunction "I_4") (pintype "input"))
    )
    (net (code "75") (name "Net-(IC6B-OUT)") (class "Default")
      (node (ref "IC6") (pin "7") (pinfunction "OUT_7") (pintype "output"))
      (node (ref "JP15") (pin "8") (pinfunction "8_8") (pintype "passive"))
      (node (ref "JP5") (pin "6") (pinfunction "6_6") (pintype "passive"))
      (node (ref "U$4") (pin "5") (pinfunction "O_5") (pintype "output"))
    )
    (net (code "76") (name "Net-(IC6C-+IN)") (class "Default")
      (node (ref "IC6") (pin "10") (pinfunction "+IN_10") (pintype "input"))
      (node (ref "U$5") (pin "2") (pinfunction "I_2") (pintype "input"))
    )
    (net (code "77") (name "Net-(IC6C-OUT)") (class "Default")
      (node (ref "IC6") (pin "8") (pinfunction "OUT_8") (pintype "output"))
      (node (ref "JP15") (pin "9") (pinfunction "9_9") (pintype "passive"))
      (node (ref "JP5") (pin "7") (pinfunction "7_7") (pintype "passive"))
      (node (ref "U$5") (pin "7") (pinfunction "O_7") (pintype "output"))
    )
    (net (code "78") (name "Net-(IC6D-+IN)") (class "Default")
      (node (ref "IC6") (pin "12") (pinfunction "+IN_12") (pintype "input"))
      (node (ref "U$5") (pin "4") (pinfunction "I_4") (pintype "input"))
    )
    (net (code "79") (name "Net-(IC6D-OUT)") (class "Default")
      (node (ref "IC6") (pin "14") (pinfunction "OUT_14") (pintype "output"))
      (node (ref "JP15") (pin "10") (pinfunction "10_10") (pintype "passive"))
      (node (ref "JP5") (pin "8") (pinfunction "8_8") (pintype "passive"))
      (node (ref "U$5") (pin "5") (pinfunction "O_5") (pintype "output"))
    )
    (net (code "80") (name "Net-(IC8-CD+)") (class "Default")
      (node (ref "IC8") (pin "10") (pinfunction "CD+_10") (pintype "passive"))
      (node (ref "SJ10") (pin "1") (pinfunction "1_1") (pintype "passive"))
      (node (ref "SJ11") (pin "1") (pinfunction "1_1") (pintype "passive"))
      (node (ref "SJ12") (pin "1") (pinfunction "1_1") (pintype "passive"))
    )
    (net (code "81") (name "Net-(IC8-GND)") (class "Default")
      (node (ref "IC8") (pin "9") (pinfunction "GND_9") (pintype "power_in"))
      (node (ref "SJ7") (pin "1") (pinfunction "1_1") (pintype "passive"))
      (node (ref "SJ8") (pin "1") (pinfunction "1_1") (pintype "passive"))
      (node (ref "SJ9") (pin "1") (pinfunction "1_1") (pintype "passive"))
    )
    (net (code "82") (name "Net-(IC8-O1)") (class "Default")
      (node (ref "IC8") (pin "18") (pinfunction "O1_18") (pintype "open_collector"))
      (node (ref "JP6") (pin "1") (pinfunction "1_1") (pintype "passive"))
      (node (ref "Q9") (pin "3") (pinfunction "D_3") (pintype "passive"))
    )
    (net (code "83") (name "Net-(IC8-O2)") (class "Default")
      (node (ref "IC8") (pin "17") (pinfunction "O2_17") (pintype "open_collector"))
      (node (ref "JP6") (pin "2") (pinfunction "2_2") (pintype "passive"))
      (node (ref "Q10") (pin "3") (pinfunction "D_3") (pintype "passive"))
    )
    (net (code "84") (name "Net-(IC8-O3)") (class "Default")
      (node (ref "IC8") (pin "16") (pinfunction "O3_16") (pintype "open_collector"))
      (node (ref "JP6") (pin "3") (pinfunction "3_3") (pintype "passive"))
      (node (ref "Q11") (pin "3") (pinfunction "D_3") (pintype "passive"))
    )
    (net (code "85") (name "Net-(IC8-O4)") (class "Default")
      (node (ref "IC8") (pin "15") (pinfunction "O4_15") (pintype "open_collector"))
      (node (ref "JP6") (pin "4") (pinfunction "4_4") (pintype "passive"))
      (node (ref "Q12") (pin "3") (pinfunction "D_3") (pintype "passive"))
    )
    (net (code "86") (name "Net-(IC8-O5)") (class "Default")
      (node (ref "IC8") (pin "14") (pinfunction "O5_14") (pintype "open_collector"))
      (node (ref "JP6") (pin "5") (pinfunction "5_5") (pintype "passive"))
      (node (ref "Q13") (pin "3") (pinfunction "D_3") (pintype "passive"))
    )
    (net (code "87") (name "Net-(IC8-O6)") (class "Default")
      (node (ref "IC8") (pin "13") (pinfunction "O6_13") (pintype "open_collector"))
      (node (ref "JP6") (pin "6") (pinfunction "6_6") (pintype "passive"))
      (node (ref "Q14") (pin "3") (pinfunction "D_3") (pintype "passive"))
    )
    (net (code "88") (name "Net-(IC8-O7)") (class "Default")
      (node (ref "IC8") (pin "12") (pinfunction "O7_12") (pintype "open_collector"))
      (node (ref "JP6") (pin "7") (pinfunction "7_7") (pintype "passive"))
      (node (ref "Q15") (pin "3") (pinfunction "D_3") (pintype "passive"))
    )
    (net (code "89") (name "Net-(IC8-O8)") (class "Default")
      (node (ref "IC8") (pin "11") (pinfunction "O8_11") (pintype "open_collector"))
      (node (ref "JP6") (pin "8") (pinfunction "8_8") (pintype "passive"))
      (node (ref "Q16") (pin "3") (pinfunction "D_3") (pintype "passive"))
    )
    (net (code "90") (name "Net-(IC9A-+IN)") (class "Default")
      (node (ref "IC9") (pin "3") (pinfunction "+IN_3") (pintype "input"))
      (node (ref "U$2") (pin "2") (pinfunction "I_2") (pintype "input"))
    )
    (net (code "91") (name "Net-(IC9A-OUT)") (class "Default")
      (node (ref "IC9") (pin "1") (pinfunction "OUT_1") (pintype "output"))
      (node (ref "JP15") (pin "1") (pinfunction "1_1") (pintype "passive"))
      (node (ref "JP5") (pin "1") (pinfunction "1_1") (pintype "passive"))
      (node (ref "U$2") (pin "7") (pinfunction "O_7") (pintype "output"))
    )
    (net (code "92") (name "Net-(IC9B-+IN)") (class "Default")
      (node (ref "IC9") (pin "5") (pinfunction "+IN_5") (pintype "input"))
      (node (ref "U$2") (pin "4") (pinfunction "I_4") (pintype "input"))
    )
    (net (code "93") (name "Net-(IC9B-OUT)") (class "Default")
      (node (ref "IC9") (pin "7") (pinfunction "OUT_7") (pintype "output"))
      (node (ref "JP15") (pin "2") (pinfunction "2_2") (pintype "passive"))
      (node (ref "JP5") (pin "2") (pinfunction "2_2") (pintype "passive"))
      (node (ref "U$2") (pin "5") (pinfunction "O_5") (pintype "output"))
    )
    (net (code "94") (name "Net-(IC9C-+IN)") (class "Default")
      (node (ref "IC9") (pin "10") (pinfunction "+IN_10") (pintype "input"))
      (node (ref "U$3") (pin "2") (pinfunction "I_2") (pintype "input"))
    )
    (net (code "95") (name "Net-(IC9C-OUT)") (class "Default")
      (node (ref "IC9") (pin "8") (pinfunction "OUT_8") (pintype "output"))
      (node (ref "JP15") (pin "3") (pinfunction "3_3") (pintype "passive"))
      (node (ref "JP5") (pin "3") (pinfunction "3_3") (pintype "passive"))
      (node (ref "U$3") (pin "7") (pinfunction "O_7") (pintype "output"))
    )
    (net (code "96") (name "Net-(IC9D-+IN)") (class "Default")
      (node (ref "IC9") (pin "12") (pinfunction "+IN_12") (pintype "input"))
      (node (ref "U$3") (pin "4") (pinfunction "I_4") (pintype "input"))
    )
    (net (code "97") (name "Net-(IC9D-OUT)") (class "Default")
      (node (ref "IC9") (pin "14") (pinfunction "OUT_14") (pintype "output"))
      (node (ref "JP15") (pin "4") (pinfunction "4_4") (pintype "passive"))
      (node (ref "JP5") (pin "4") (pinfunction "4_4") (pintype "passive"))
      (node (ref "U$3") (pin "5") (pinfunction "O_5") (pintype "output"))
    )
    (net (code "98") (name "Net-(J1-Pad4)") (class "Default")
      (node (ref "J1") (pin "4") (pinfunction "4_4") (pintype "passive"))
      (node (ref "J2") (pin "4") (pinfunction "4_4") (pintype "passive"))
    )
    (net (code "99") (name "Net-(J1-Pad5)") (class "Default")
      (node (ref "J1") (pin "5") (pinfunction "5_5") (pintype "passive"))
      (node (ref "J2") (pin "5") (pinfunction "5_5") (pintype "passive"))
    )
    (net (code "100") (name "Net-(J1-Pad8)") (class "Default")
      (node (ref "J1") (pin "8") (pinfunction "8_8") (pintype "passive"))
      (node (ref "J2") (pin "8") (pinfunction "8_8") (pintype "passive"))
    )
    (net (code "101") (name "Net-(JP13-Pad1)") (class "Default")
      (node (ref "JP13") (pin "1") (pinfunction "1_1") (pintype "passive"))
      (node (ref "JP3") (pin "1") (pinfunction "1_1") (pintype "passive"))
      (node (ref "RN4") (pin "1") (pinfunction "1_1") (pintype "passive"))
      (node (ref "RN5") (pin "9") (pinfunction "9_9") (pintype "passive"))
    )
    (net (code "102") (name "Net-(JP14-Pad1)") (class "Default")
      (node (ref "JP14") (pin "1") (pinfunction "1_1") (pintype "passive"))
      (node (ref "JP2") (pin "1") (pinfunction "1_1") (pintype "passive"))
      (node (ref "RN1") (pin "1") (pinfunction "1_1") (pintype "passive"))
      (node (ref "RN2") (pin "9") (pinfunction "9_9") (pintype "passive"))
    )
    (net (code "103") (name "Net-(Q1-G)") (class "Default")
      (node (ref "Q1") (pin "1") (pinfunction "G_1") (pintype "passive"))
      (node (ref "R3") (pin "2") (pinfunction "2_2") (pintype "passive"))
    )
    (net (code "104") (name "Net-(Q2-G)") (class "Default")
      (node (ref "Q2") (pin "1") (pinfunction "G_1") (pintype "passive"))
      (node (ref "R4") (pin "2") (pinfunction "2_2") (pintype "passive"))
    )
    (net (code "105") (name "Net-(Q3-G)") (class "Default")
      (node (ref "Q3") (pin "1") (pinfunction "G_1") (pintype "passive"))
      (node (ref "R5") (pin "2") (pinfunction "2_2") (pintype "passive"))
    )
    (net (code "106") (name "Net-(Q4-G)") (class "Default")
      (node (ref "Q4") (pin "1") (pinfunction "G_1") (pintype "passive"))
      (node (ref "R6") (pin "2") (pinfunction "2_2") (pintype "passive"))
    )
    (net (code "107") (name "Net-(Q5-G)") (class "Default")
      (node (ref "Q5") (pin "1") (pinfunction "G_1") (pintype "passive"))
      (node (ref "R7") (pin "2") (pinfunction "2_2") (pintype "passive"))
    )
    (net (code "108") (name "Net-(Q6-G)") (class "Default")
      (node (ref "Q6") (pin "1") (pinfunction "G_1") (pintype "passive"))
      (node (ref "R8") (pin "2") (pinfunction "2_2") (pintype "passive"))
    )
    (net (code "109") (name "Net-(Q7-G)") (class "Default")
      (node (ref "Q7") (pin "1") (pinfunction "G_1") (pintype "passive"))
      (node (ref "R9") (pin "2") (pinfunction "2_2") (pintype "passive"))
    )
    (net (code "110") (name "Net-(Q8-G)") (class "Default")
      (node (ref "Q8") (pin "1") (pinfunction "G_1") (pintype "passive"))
      (node (ref "R10") (pin "2") (pinfunction "2_2") (pintype "passive"))
    )
    (net (code "111") (name "Net-(Q9-G)") (class "Default")
      (node (ref "Q9") (pin "1") (pinfunction "G_1") (pintype "passive"))
      (node (ref "R11") (pin "2") (pinfunction "2_2") (pintype "passive"))
    )
    (net (code "112") (name "Net-(Q10-G)") (class "Default")
      (node (ref "Q10") (pin "1") (pinfunction "G_1") (pintype "passive"))
      (node (ref "R12") (pin "2") (pinfunction "2_2") (pintype "passive"))
    )
    (net (code "113") (name "Net-(Q11-G)") (class "Default")
      (node (ref "Q11") (pin "1") (pinfunction "G_1") (pintype "passive"))
      (node (ref "R13") (pin "2") (pinfunction "2_2") (pintype "passive"))
    )
    (net (code "114") (name "Net-(Q12-G)") (class "Default")
      (node (ref "Q12") (pin "1") (pinfunction "G_1") (pintype "passive"))
      (node (ref "R14") (pin "2") (pinfunction "2_2") (pintype "passive"))
    )
    (net (code "115") (name "Net-(Q13-G)") (class "Default")
      (node (ref "Q13") (pin "1") (pinfunction "G_1") (pintype "passive"))
      (node (ref "R15") (pin "2") (pinfunction "2_2") (pintype "passive"))
    )
    (net (code "116") (name "Net-(Q14-G)") (class "Default")
      (node (ref "Q14") (pin "1") (pinfunction "G_1") (pintype "passive"))
      (node (ref "R16") (pin "2") (pinfunction "2_2") (pintype "passive"))
    )
    (net (code "117") (name "Net-(Q15-G)") (class "Default")
      (node (ref "Q15") (pin "1") (pinfunction "G_1") (pintype "passive"))
      (node (ref "R17") (pin "2") (pinfunction "2_2") (pintype "passive"))
    )
    (net (code "118") (name "Net-(Q16-G)") (class "Default")
      (node (ref "Q16") (pin "1") (pinfunction "G_1") (pintype "passive"))
      (node (ref "R18") (pin "2") (pinfunction "2_2") (pintype "passive"))
    )
    (net (code "119") (name "Net-(RN1B-1)") (class "Default")
      (node (ref "JP14") (pin "2") (pinfunction "2_2") (pintype "passive"))
      (node (ref "JP2") (pin "2") (pinfunction "2_2") (pintype "passive"))
      (node (ref "RN1") (pin "2") (pinfunction "1_2") (pintype "passive"))
      (node (ref "RN2") (pin "8") (pinfunction "8_8") (pintype "passive"))
    )
    (net (code "120") (name "Net-(RN1C-1)") (class "Default")
      (node (ref "JP14") (pin "3") (pinfunction "3_3") (pintype "passive"))
      (node (ref "JP2") (pin "3") (pinfunction "3_3") (pintype "passive"))
      (node (ref "RN1") (pin "3") (pinfunction "1_3") (pintype "passive"))
      (node (ref "RN2") (pin "7") (pinfunction "7_7") (pintype "passive"))
    )
    (net (code "121") (name "Net-(RN1D-1)") (class "Default")
      (node (ref "JP14") (pin "4") (pinfunction "4_4") (pintype "passive"))
      (node (ref "JP2") (pin "4") (pinfunction "4_4") (pintype "passive"))
      (node (ref "RN1") (pin "4") (pinfunction "1_4") (pintype "passive"))
      (node (ref "RN2") (pin "6") (pinfunction "6_6") (pintype "passive"))
    )
    (net (code "122") (name "Net-(RN1E-1)") (class "Default")
      (node (ref "JP14") (pin "7") (pinfunction "7_7") (pintype "passive"))
      (node (ref "JP2") (pin "5") (pinfunction "5_5") (pintype "passive"))
      (node (ref "RN1") (pin "5") (pinfunction "1_5") (pintype "passive"))
      (node (ref "RN2") (pin "5") (pinfunction "5_5") (pintype "passive"))
    )
    (net (code "123") (name "Net-(RN1F-1)") (class "Default")
      (node (ref "JP14") (pin "8") (pinfunction "8_8") (pintype "passive"))
      (node (ref "JP2") (pin "6") (pinfunction "6_6") (pintype "passive"))
      (node (ref "RN1") (pin "6") (pinfunction "1_6") (pintype "passive"))
      (node (ref "RN2") (pin "4") (pinfunction "4_4") (pintype "passive"))
    )
    (net (code "124") (name "Net-(RN1G-1)") (class "Default")
      (node (ref "JP14") (pin "9") (pinfunction "9_9") (pintype "passive"))
      (node (ref "JP2") (pin "7") (pinfunction "7_7") (pintype "passive"))
      (node (ref "RN1") (pin "7") (pinfunction "1_7") (pintype "passive"))
      (node (ref "RN2") (pin "3") (pinfunction "3_3") (pintype "passive"))
    )
    (net (code "125") (name "Net-(RN1H-1)") (class "Default")
      (node (ref "JP14") (pin "10") (pinfunction "10_10") (pintype "passive"))
      (node (ref "JP2") (pin "8") (pinfunction "8_8") (pintype "passive"))
      (node (ref "RN1") (pin "8") (pinfunction "1_8") (pintype "passive"))
      (node (ref "RN2") (pin "2") (pinfunction "2_2") (pintype "passive"))
    )
    (net (code "126") (name "Net-(RN4B-1)") (class "Default")
      (node (ref "JP13") (pin "2") (pinfunction "2_2") (pintype "passive"))
      (node (ref "JP3") (pin "2") (pinfunction "2_2") (pintype "passive"))
      (node (ref "RN4") (pin "2") (pinfunction "1_2") (pintype "passive"))
      (node (ref "RN5") (pin "8") (pinfunction "8_8") (pintype "passive"))
    )
    (net (code "127") (name "Net-(RN4C-1)") (class "Default")
      (node (ref "JP13") (pin "3") (pinfunction "3_3") (pintype "passive"))
      (node (ref "JP3") (pin "3") (pinfunction "3_3") (pintype "passive"))
      (node (ref "RN4") (pin "3") (pinfunction "1_3") (pintype "passive"))
      (node (ref "RN5") (pin "7") (pinfunction "7_7") (pintype "passive"))
    )
    (net (code "128") (name "Net-(RN4D-1)") (class "Default")
      (node (ref "JP13") (pin "4") (pinfunction "4_4") (pintype "passive"))
      (node (ref "JP3") (pin "4") (pinfunction "4_4") (pintype "passive"))
      (node (ref "RN4") (pin "4") (pinfunction "1_4") (pintype "passive"))
      (node (ref "RN5") (pin "6") (pinfunction "6_6") (pintype "passive"))
    )
    (net (code "129") (name "Net-(RN4E-1)") (class "Default")
      (node (ref "JP13") (pin "7") (pinfunction "7_7") (pintype "passive"))
      (node (ref "JP3") (pin "5") (pinfunction "5_5") (pintype "passive"))
      (node (ref "RN4") (pin "5") (pinfunction "1_5") (pintype "passive"))
      (node (ref "RN5") (pin "5") (pinfunction "5_5") (pintype "passive"))
    )
    (net (code "130") (name "Net-(RN4F-1)") (class "Default")
      (node (ref "JP13") (pin "8") (pinfunction "8_8") (pintype "passive"))
      (node (ref "JP3") (pin "6") (pinfunction "6_6") (pintype "passive"))
      (node (ref "RN4") (pin "6") (pinfunction "1_6") (pintype "passive"))
      (node (ref "RN5") (pin "4") (pinfunction "4_4") (pintype "passive"))
    )
    (net (code "131") (name "Net-(RN4G-1)") (class "Default")
      (node (ref "JP13") (pin "9") (pinfunction "9_9") (pintype "passive"))
      (node (ref "JP3") (pin "7") (pinfunction "7_7") (pintype "passive"))
      (node (ref "RN4") (pin "7") (pinfunction "1_7") (pintype "passive"))
      (node (ref "RN5") (pin "3") (pinfunction "3_3") (pintype "passive"))
    )
    (net (code "132") (name "Net-(RN4H-1)") (class "Default")
      (node (ref "JP13") (pin "10") (pinfunction "10_10") (pintype "passive"))
      (node (ref "JP3") (pin "8") (pinfunction "8_8") (pintype "passive"))
      (node (ref "RN4") (pin "8") (pinfunction "1_8") (pintype "passive"))
      (node (ref "RN5") (pin "2") (pinfunction "2_2") (pintype "passive"))
    )
    (net (code "133") (name "SCK") (class "Default")
      (node (ref "IC1") (pin "7") (pinfunction "CLK_7") (pintype "input"))
      (node (ref "IC3") (pin "11") (pinfunction "SCK_11") (pintype "input"))
      (node (ref "IC4") (pin "7") (pinfunction "CLK_7") (pintype "input"))
      (node (ref "IC5") (pin "11") (pinfunction "SCK_11") (pintype "input"))
      (node (ref "R19") (pin "1") (pinfunction "1_1") (pintype "passive"))
      (node (ref "U$1") (pin "PB3") (pinfunction "PB3_PB3") (pintype "bidirectional"))
    )
    (net (code "134") (name "SLNK1") (class "Default")
      (node (ref "IC3") (pin "14") (pinfunction "SER_14") (pintype "input"))
      (node (ref "IC5") (pin "9") (pinfunction "QH*_9") (pintype "tri_state"))
    )
    (net (code "135") (name "unconnected-(H1-MOUNT-PadB3,3)") (class "Default")
      (node (ref "H1") (pin "B3,3") (pinfunction "MOUNT_B3,3") (pintype "passive"))
    )
    (net (code "136") (name "unconnected-(H2-MOUNT-PadB3,3)") (class "Default")
      (node (ref "H2") (pin "B3,3") (pinfunction "MOUNT_B3,3") (pintype "passive"))
    )
    (net (code "137") (name "unconnected-(H3-MOUNT-PadB3,3)") (class "Default")
      (node (ref "H3") (pin "B3,3") (pinfunction "MOUNT_B3,3") (pintype "passive"))
    )
    (net (code "138") (name "unconnected-(H4-MOUNT-PadB3,3)") (class "Default")
      (node (ref "H4") (pin "B3,3") (pinfunction "MOUNT_B3,3") (pintype "passive"))
    )
    (net (code "139") (name "unconnected-(IC3A-QH*-Pad9)") (class "Default")
      (node (ref "IC3") (pin "9") (pinfunction "QH*_9") (pintype "tri_state"))
    )
    (net (code "140") (name "unconnected-(IC7-RS-Pad8)") (class "Default")
      (node (ref "IC7") (pin "8") (pinfunction "RS_8") (pintype "input"))
    )
    (net (code "141") (name "unconnected-(IC7-VREF-Pad5)") (class "Default")
      (node (ref "IC7") (pin "5") (pinfunction "VREF_5") (pintype "output"))
    )
    (net (code "142") (name "unconnected-(J3-Pad2)") (class "Default")
      (node (ref "J3") (pin "2") (pinfunction "2_2") (pintype "passive"))
    )
    (net (code "143") (name "unconnected-(JP4-Pad1)") (class "Default")
      (node (ref "JP4") (pin "1") (pinfunction "1_1") (pintype "passive"))
    )
    (net (code "144") (name "unconnected-(JP4-Pad2)") (class "Default")
      (node (ref "JP4") (pin "2") (pinfunction "2_2") (pintype "passive"))
    )
    (net (code "145") (name "unconnected-(JP4-Pad3)") (class "Default")
      (node (ref "JP4") (pin "3") (pinfunction "3_3") (pintype "passive"))
    )
    (net (code "146") (name "unconnected-(JP4-Pad4)") (class "Default")
      (node (ref "JP4") (pin "4") (pinfunction "4_4") (pintype "passive"))
    )
    (net (code "147") (name "unconnected-(JP7-Pad1)") (class "Default")
      (node (ref "JP7") (pin "1") (pinfunction "1_1") (pintype "passive"))
    )
    (net (code "148") (name "unconnected-(JP7-Pad2)") (class "Default")
      (node (ref "JP7") (pin "2") (pinfunction "2_2") (pintype "passive"))
    )
    (net (code "149") (name "unconnected-(JP7-Pad3)") (class "Default")
      (node (ref "JP7") (pin "3") (pinfunction "3_3") (pintype "passive"))
    )
    (net (code "150") (name "unconnected-(JP7-Pad4)") (class "Default")
      (node (ref "JP7") (pin "4") (pinfunction "4_4") (pintype "passive"))
    )
    (net (code "151") (name "unconnected-(JP7-Pad5)") (class "Default")
      (node (ref "JP7") (pin "5") (pinfunction "5_5") (pintype "passive"))
    )
    (net (code "152") (name "unconnected-(JP7-Pad6)") (class "Default")
      (node (ref "JP7") (pin "6") (pinfunction "6_6") (pintype "passive"))
    )
    (net (code "153") (name "unconnected-(JP8-Pad1)") (class "Default")
      (node (ref "JP8") (pin "1") (pinfunction "1_1") (pintype "passive"))
    )
    (net (code "154") (name "unconnected-(JP8-Pad2)") (class "Default")
      (node (ref "JP8") (pin "2") (pinfunction "2_2") (pintype "passive"))
    )
    (net (code "155") (name "unconnected-(JP8-Pad3)") (class "Default")
      (node (ref "JP8") (pin "3") (pinfunction "3_3") (pintype "passive"))
    )
    (net (code "156") (name "unconnected-(JP8-Pad4)") (class "Default")
      (node (ref "JP8") (pin "4") (pinfunction "4_4") (pintype "passive"))
    )
    (net (code "157") (name "unconnected-(JP9-Pad1)") (class "Default")
      (node (ref "JP9") (pin "1") (pinfunction "1_1") (pintype "passive"))
    )
    (net (code "158") (name "unconnected-(JP9-Pad2)") (class "Default")
      (node (ref "JP9") (pin "2") (pinfunction "2_2") (pintype "passive"))
    )
    (net (code "159") (name "unconnected-(JP9-Pad3)") (class "Default")
      (node (ref "JP9") (pin "3") (pinfunction "3_3") (pintype "passive"))
    )
    (net (code "160") (name "unconnected-(JP9-Pad4)") (class "Default")
      (node (ref "JP9") (pin "4") (pinfunction "4_4") (pintype "passive"))
    )
    (net (code "161") (name "unconnected-(JP10-Pad1)") (class "Default")
      (node (ref "JP10") (pin "1") (pinfunction "1_1") (pintype "passive"))
    )
    (net (code "162") (name "unconnected-(JP10-Pad2)") (class "Default")
      (node (ref "JP10") (pin "2") (pinfunction "2_2") (pintype "passive"))
    )
    (net (code "163") (name "unconnected-(JP10-Pad3)") (class "Default")
      (node (ref "JP10") (pin "3") (pinfunction "3_3") (pintype "passive"))
    )
    (net (code "164") (name "unconnected-(JP10-Pad4)") (class "Default")
      (node (ref "JP10") (pin "4") (pinfunction "4_4") (pintype "passive"))
    )
    (net (code "165") (name "unconnected-(JP11-Pad1)") (class "Default")
      (node (ref "JP11") (pin "1") (pinfunction "1_1") (pintype "passive"))
    )
    (net (code "166") (name "unconnected-(JP11-Pad2)") (class "Default")
      (node (ref "JP11") (pin "2") (pinfunction "2_2") (pintype "passive"))
    )
    (net (code "167") (name "unconnected-(JP11-Pad3)") (class "Default")
      (node (ref "JP11") (pin "3") (pinfunction "3_3") (pintype "passive"))
    )
    (net (code "168") (name "unconnected-(JP11-Pad4)") (class "Default")
      (node (ref "JP11") (pin "4") (pinfunction "4_4") (pintype "passive"))
    )
    (net (code "169") (name "unconnected-(JP11-Pad5)") (class "Default")
      (node (ref "JP11") (pin "5") (pinfunction "5_5") (pintype "passive"))
    )
    (net (code "170") (name "unconnected-(JP11-Pad6)") (class "Default")
      (node (ref "JP11") (pin "6") (pinfunction "6_6") (pintype "passive"))
    )
    (net (code "171") (name "unconnected-(JP13-Pad5)") (class "Default")
      (node (ref "JP13") (pin "5") (pinfunction "5_5") (pintype "passive"))
    )
    (net (code "172") (name "unconnected-(JP13-Pad6)") (class "Default")
      (node (ref "JP13") (pin "6") (pinfunction "6_6") (pintype "passive"))
    )
    (net (code "173") (name "unconnected-(JP14-Pad5)") (class "Default")
      (node (ref "JP14") (pin "5") (pinfunction "5_5") (pintype "passive"))
    )
    (net (code "174") (name "unconnected-(JP14-Pad6)") (class "Default")
      (node (ref "JP14") (pin "6") (pinfunction "6_6") (pintype "passive"))
    )
    (net (code "175") (name "unconnected-(JP15-Pad5)") (class "Default")
      (node (ref "JP15") (pin "5") (pinfunction "5_5") (pintype "passive"))
    )
    (net (code "176") (name "unconnected-(JP15-Pad6)") (class "Default")
      (node (ref "JP15") (pin "6") (pinfunction "6_6") (pintype "passive"))
    )
    (net (code "177") (name "unconnected-(U$1-PadBOOT0)") (class "Default")
      (node (ref "U$1") (pin "BOOT0") (pinfunction "BOOT0_BOOT0") (pintype "bidirectional"))
    )
    (net (code "178") (name "unconnected-(U$1-PadIOREF2)") (class "Default")
      (node (ref "U$1") (pin "IOREF2") (pinfunction "IOREF2_IOREF2") (pintype "input"))
    )
    (net (code "179") (name "unconnected-(U$1-PadNC1-PF7)") (class "Default")
      (node (ref "U$1") (pin "NC1-PF7") (pinfunction "NC1-PF7_NC1-PF7") (pintype "bidirectional"))
    )
    (net (code "180") (name "unconnected-(U$1-PadNC2-PF6)") (class "Default")
      (node (ref "U$1") (pin "NC2-PF6") (pinfunction "NC2-PF6_NC2-PF6") (pintype "bidirectional"))
    )
    (net (code "181") (name "unconnected-(U$1-PadNC3)") (class "Default")
      (node (ref "U$1") (pin "NC3") (pinfunction "NC3_NC3") (pintype "no_connect"))
    )
    (net (code "182") (name "unconnected-(U$1-PadNC4)") (class "Default")
      (node (ref "U$1") (pin "NC4") (pinfunction "NC4_NC4") (pintype "no_connect"))
    )
    (net (code "183") (name "unconnected-(U$1-PadNC5-PD8)") (class "Default")
      (node (ref "U$1") (pin "NC5-PD8") (pinfunction "NC5-PD8_NC5-PD8") (pintype "bidirectional"))
    )
    (net (code "184") (name "unconnected-(U$1-PadNC6-PB11)") (class "Default")
      (node (ref "U$1") (pin "NC6-PB11") (pinfunction "NC6-PB11_NC6-PB11") (pintype "no_connect"))
    )
    (net (code "185") (name "unconnected-(U$1-PadNC7-PF5)") (class "Default")
      (node (ref "U$1") (pin "NC7-PF5") (pinfunction "NC7-PF5_NC7-PF5") (pintype "bidirectional"))
    )
    (net (code "186") (name "unconnected-(U$1-PadNC8-PF4)") (class "Default")
      (node (ref "U$1") (pin "NC8-PF4") (pinfunction "NC8-PF4_NC8-PF4") (pintype "bidirectional"))
    )
    (net (code "187") (name "unconnected-(U$1-PadNRESET)") (class "Default")
      (node (ref "U$1") (pin "NRESET") (pinfunction "NRESET_NRESET") (pintype "input"))
    )
    (net (code "188") (name "unconnected-(U$1-PadPA0)") (class "Default")
      (node (ref "U$1") (pin "PA0") (pinfunction "PA0_PA0") (pintype "bidirectional"))
    )
    (net (code "189") (name "unconnected-(U$1-PadPA1)") (class "Default")
      (node (ref "U$1") (pin "PA1") (pinfunction "PA1_PA1") (pintype "bidirectional"))
    )
    (net (code "190") (name "unconnected-(U$1-PadPA2)") (class "Default")
      (node (ref "U$1") (pin "PA2") (pinfunction "PA2_PA2") (pintype "bidirectional"))
    )
    (net (code "191") (name "unconnected-(U$1-PadPA3)") (class "Default")
      (node (ref "U$1") (pin "PA3") (pinfunction "PA3_PA3") (pintype "bidirectional"))
    )
    (net (code "192") (name "unconnected-(U$1-PadPA4)") (class "Default")
      (node (ref "U$1") (pin "PA4") (pinfunction "PA4_PA4") (pintype "bidirectional"))
    )
    (net (code "193") (name "unconnected-(U$1-PadPA5)") (class "Default")
      (node (ref "U$1") (pin "PA5") (pinfunction "PA5_PA5") (pintype "bidirectional"))
    )
    (net (code "194") (name "unconnected-(U$1-PadPA6)") (class "Default")
      (node (ref "U$1") (pin "PA6") (pinfunction "PA6_PA6") (pintype "bidirectional"))
    )
    (net (code "195") (name "unconnected-(U$1-PadPA7)") (class "Default")
      (node (ref "U$1") (pin "PA7") (pinfunction "PA7_PA7") (pintype "bidirectional"))
    )
    (net (code "196") (name "unconnected-(U$1-PadPA8)") (class "Default")
      (node (ref "U$1") (pin "PA8") (pinfunction "PA8_PA8") (pintype "bidirectional"))
    )
    (net (code "197") (name "unconnected-(U$1-PadPA9)") (class "Default")
      (node (ref "U$1") (pin "PA9") (pinfunction "PA9_PA9") (pintype "bidirectional"))
    )
    (net (code "198") (name "unconnected-(U$1-PadPA10)") (class "Default")
      (node (ref "U$1") (pin "PA10") (pinfunction "PA10_PA10") (pintype "bidirectional"))
    )
    (net (code "199") (name "unconnected-(U$1-PadPA11)") (class "Default")
      (node (ref "U$1") (pin "PA11") (pinfunction "PA11_PA11") (pintype "bidirectional"))
    )
    (net (code "200") (name "unconnected-(U$1-PadPA12)") (class "Default")
      (node (ref "U$1") (pin "PA12") (pinfunction "PA12_PA12") (pintype "bidirectional"))
    )
    (net (code "201") (name "unconnected-(U$1-PadPA13)") (class "Default")
      (node (ref "U$1") (pin "PA13") (pinfunction "PA13_PA13") (pintype "bidirectional"))
    )
    (net (code "202") (name "unconnected-(U$1-PadPA14)") (class "Default")
      (node (ref "U$1") (pin "PA14") (pinfunction "PA14_PA14") (pintype "bidirectional"))
    )
    (net (code "203") (name "unconnected-(U$1-PadPA15)") (class "Default")
      (node (ref "U$1") (pin "PA15") (pinfunction "PA15_PA15") (pintype "bidirectional"))
    )
    (net (code "204") (name "unconnected-(U$1-PadPB0)") (class "Default")
      (node (ref "U$1") (pin "PB0") (pinfunction "PB0_PB0") (pintype "bidirectional"))
    )
    (net (code "205") (name "unconnected-(U$1-PadPB1)") (class "Default")
      (node (ref "U$1") (pin "PB1") (pinfunction "PB1_PB1") (pintype "bidirectional"))
    )
    (net (code "206") (name "unconnected-(U$1-PadPB2)") (class "Default")
      (node (ref "U$1") (pin "PB2") (pinfunction "PB2_PB2") (pintype "bidirectional"))
    )
    (net (code "207") (name "unconnected-(U$1-PadPB6)") (class "Default")
      (node (ref "U$1") (pin "PB6") (pinfunction "PB6_PB6") (pintype "bidirectional"))
    )
    (net (code "208") (name "unconnected-(U$1-PadPB7)") (class "Default")
      (node (ref "U$1") (pin "PB7") (pinfunction "PB7_PB7") (pintype "bidirectional"))
    )
    (net (code "209") (name "unconnected-(U$1-PadPB10)") (class "Default")
      (node (ref "U$1") (pin "PB10") (pinfunction "PB10_PB10") (pintype "bidirectional"))
    )
    (net (code "210") (name "unconnected-(U$1-PadPB12)") (class "Default")
      (node (ref "U$1") (pin "PB12") (pinfunction "PB12_PB12") (pintype "bidirectional"))
    )
    (net (code "211") (name "unconnected-(U$1-PadPB13)") (class "Default")
      (node (ref "U$1") (pin "PB13") (pinfunction "PB13_PB13") (pintype "bidirectional"))
    )
    (net (code "212") (name "unconnected-(U$1-PadPB14)") (class "Default")
      (node (ref "U$1") (pin "PB14") (pinfunction "PB14_PB14") (pintype "bidirectional"))
    )
    (net (code "213") (name "unconnected-(U$1-PadPB15)") (class "Default")
      (node (ref "U$1") (pin "PB15") (pinfunction "PB15_PB15") (pintype "bidirectional"))
    )
    (net (code "214") (name "unconnected-(U$1-PadPC0)") (class "Default")
      (node (ref "U$1") (pin "PC0") (pinfunction "PC0_PC0") (pintype "bidirectional"))
    )
    (net (code "215") (name "unconnected-(U$1-PadPC1)") (class "Default")
      (node (ref "U$1") (pin "PC1") (pinfunction "PC1_PC1") (pintype "bidirectional"))
    )
    (net (code "216") (name "unconnected-(U$1-PadPC2)") (class "Default")
      (node (ref "U$1") (pin "PC2") (pinfunction "PC2_PC2") (pintype "bidirectional"))
    )
    (net (code "217") (name "unconnected-(U$1-PadPC3)") (class "Default")
      (node (ref "U$1") (pin "PC3") (pinfunction "PC3_PC3") (pintype "bidirectional"))
    )
    (net (code "218") (name "unconnected-(U$1-PadPC4)") (class "Default")
      (node (ref "U$1") (pin "PC4") (pinfunction "PC4_PC4") (pintype "bidirectional"))
    )
    (net (code "219") (name "unconnected-(U$1-PadPC5)") (class "Default")
      (node (ref "U$1") (pin "PC5") (pinfunction "PC5_PC5") (pintype "bidirectional"))
    )
    (net (code "220") (name "unconnected-(U$1-PadPC6)") (class "Default")
      (node (ref "U$1") (pin "PC6") (pinfunction "PC6_PC6") (pintype "bidirectional"))
    )
    (net (code "221") (name "unconnected-(U$1-PadPC7)") (class "Default")
      (node (ref "U$1") (pin "PC7") (pinfunction "PC7_PC7") (pintype "bidirectional"))
    )
    (net (code "222") (name "unconnected-(U$1-PadPC8)") (class "Default")
      (node (ref "U$1") (pin "PC8") (pinfunction "PC8_PC8") (pintype "bidirectional"))
    )
    (net (code "223") (name "unconnected-(U$1-PadPC9)") (class "Default")
      (node (ref "U$1") (pin "PC9") (pinfunction "PC9_PC9") (pintype "bidirectional"))
    )
    (net (code "224") (name "unconnected-(U$1-PadPC10)") (class "Default")
      (node (ref "U$1") (pin "PC10") (pinfunction "PC10_PC10") (pintype "bidirectional"))
    )
    (net (code "225") (name "unconnected-(U$1-PadPC11)") (class "Default")
      (node (ref "U$1") (pin "PC11") (pinfunction "PC11_PC11") (pintype "bidirectional"))
    )
    (net (code "226") (name "unconnected-(U$1-PadPC12)") (class "Default")
      (node (ref "U$1") (pin "PC12") (pinfunction "PC12_PC12") (pintype "bidirectional"))
    )
    (net (code "227") (name "unconnected-(U$1-PadPC13)") (class "Default")
      (node (ref "U$1") (pin "PC13") (pinfunction "PC13_PC13") (pintype "bidirectional"))
    )
    (net (code "228") (name "unconnected-(U$1-PadPC14)") (class "Default")
      (node (ref "U$1") (pin "PC14") (pinfunction "PC14_PC14") (pintype "bidirectional"))
    )
    (net (code "229") (name "unconnected-(U$1-PadPC15)") (class "Default")
      (node (ref "U$1") (pin "PC15") (pinfunction "PC15_PC15") (pintype "bidirectional"))
    )
    (net (code "230") (name "unconnected-(U$1-PadPD2)") (class "Default")
      (node (ref "U$1") (pin "PD2") (pinfunction "PD2_PD2") (pintype "bidirectional"))
    )
    (net (code "231") (name "unconnected-(U$1-PadPF0-PH0)") (class "Default")
      (node (ref "U$1") (pin "PF0-PH0") (pinfunction "PF0-PH0_PF0-PH0") (pintype "bidirectional"))
    )
    (net (code "232") (name "unconnected-(U$1-PadPF1-PH1)") (class "Default")
      (node (ref "U$1") (pin "PF1-PH1") (pinfunction "PF1-PH1_PF1-PH1") (pintype "bidirectional"))
    )
  )
)
